# RFWBBoard.net
KiCad netlist of a schematic drawn in EAGLE
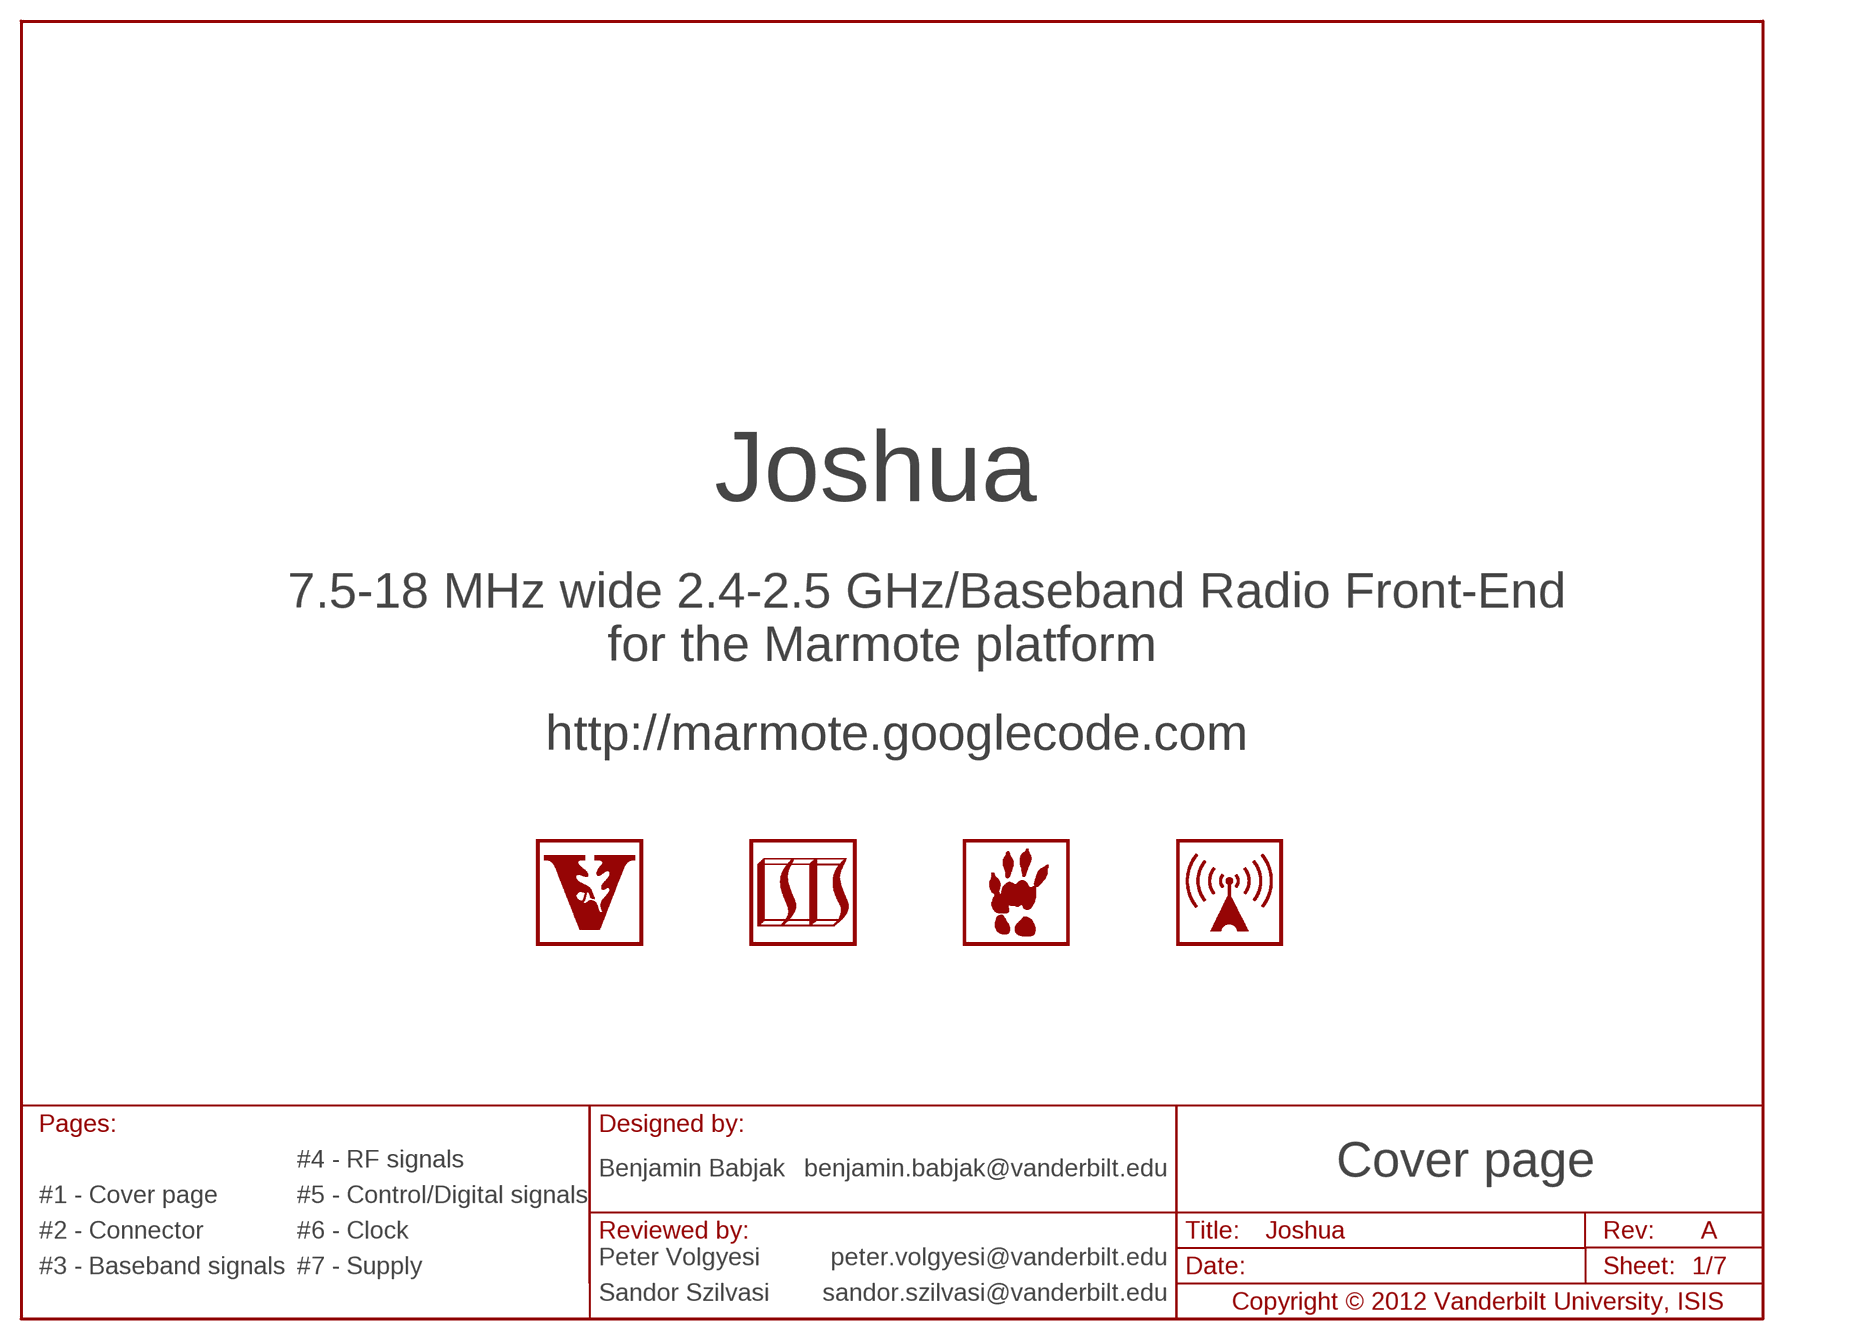
[diagram p0: schematic, sheet 1]
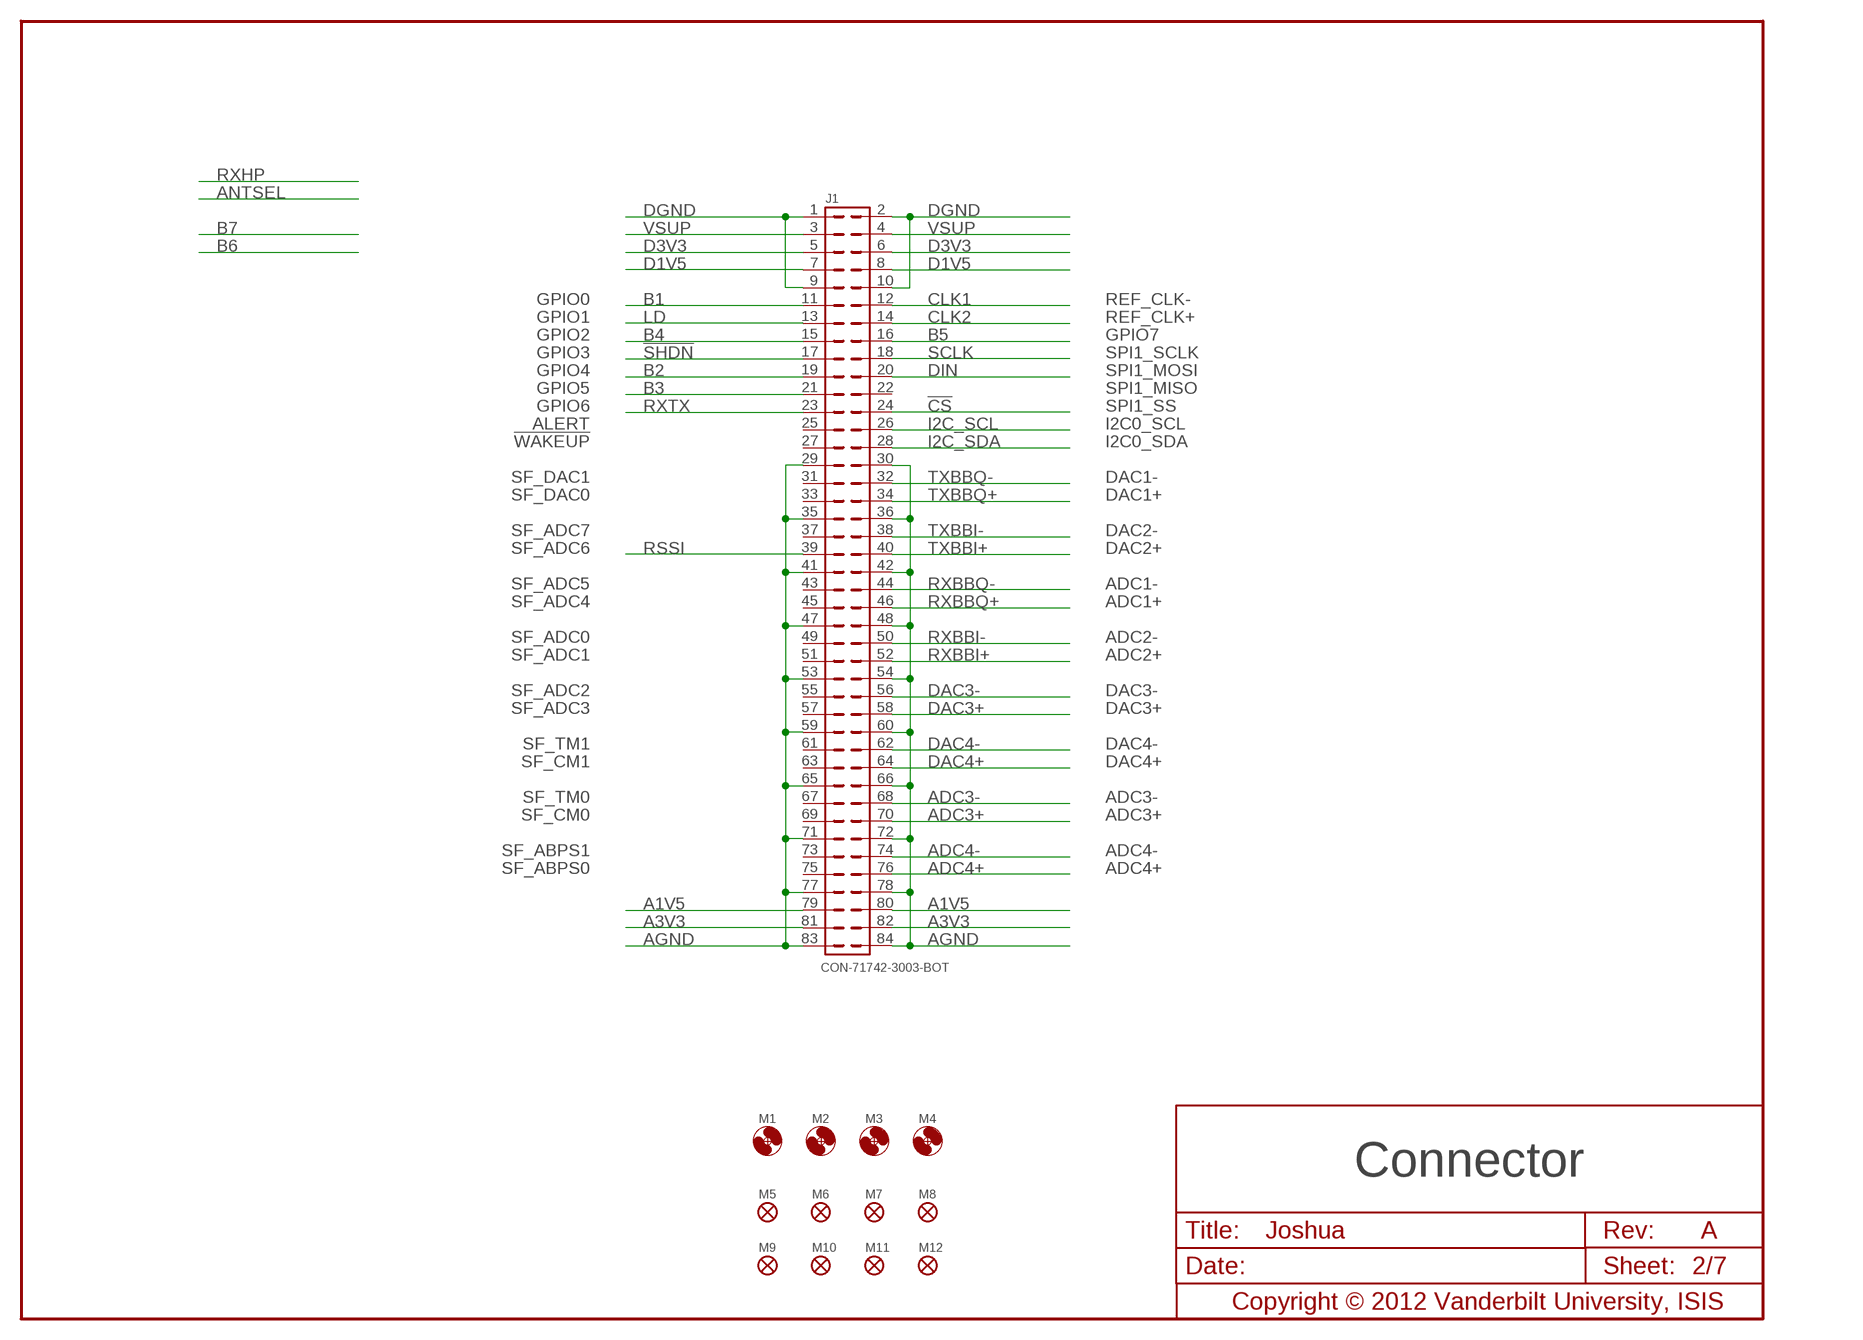
[diagram p1: schematic, sheet 2]
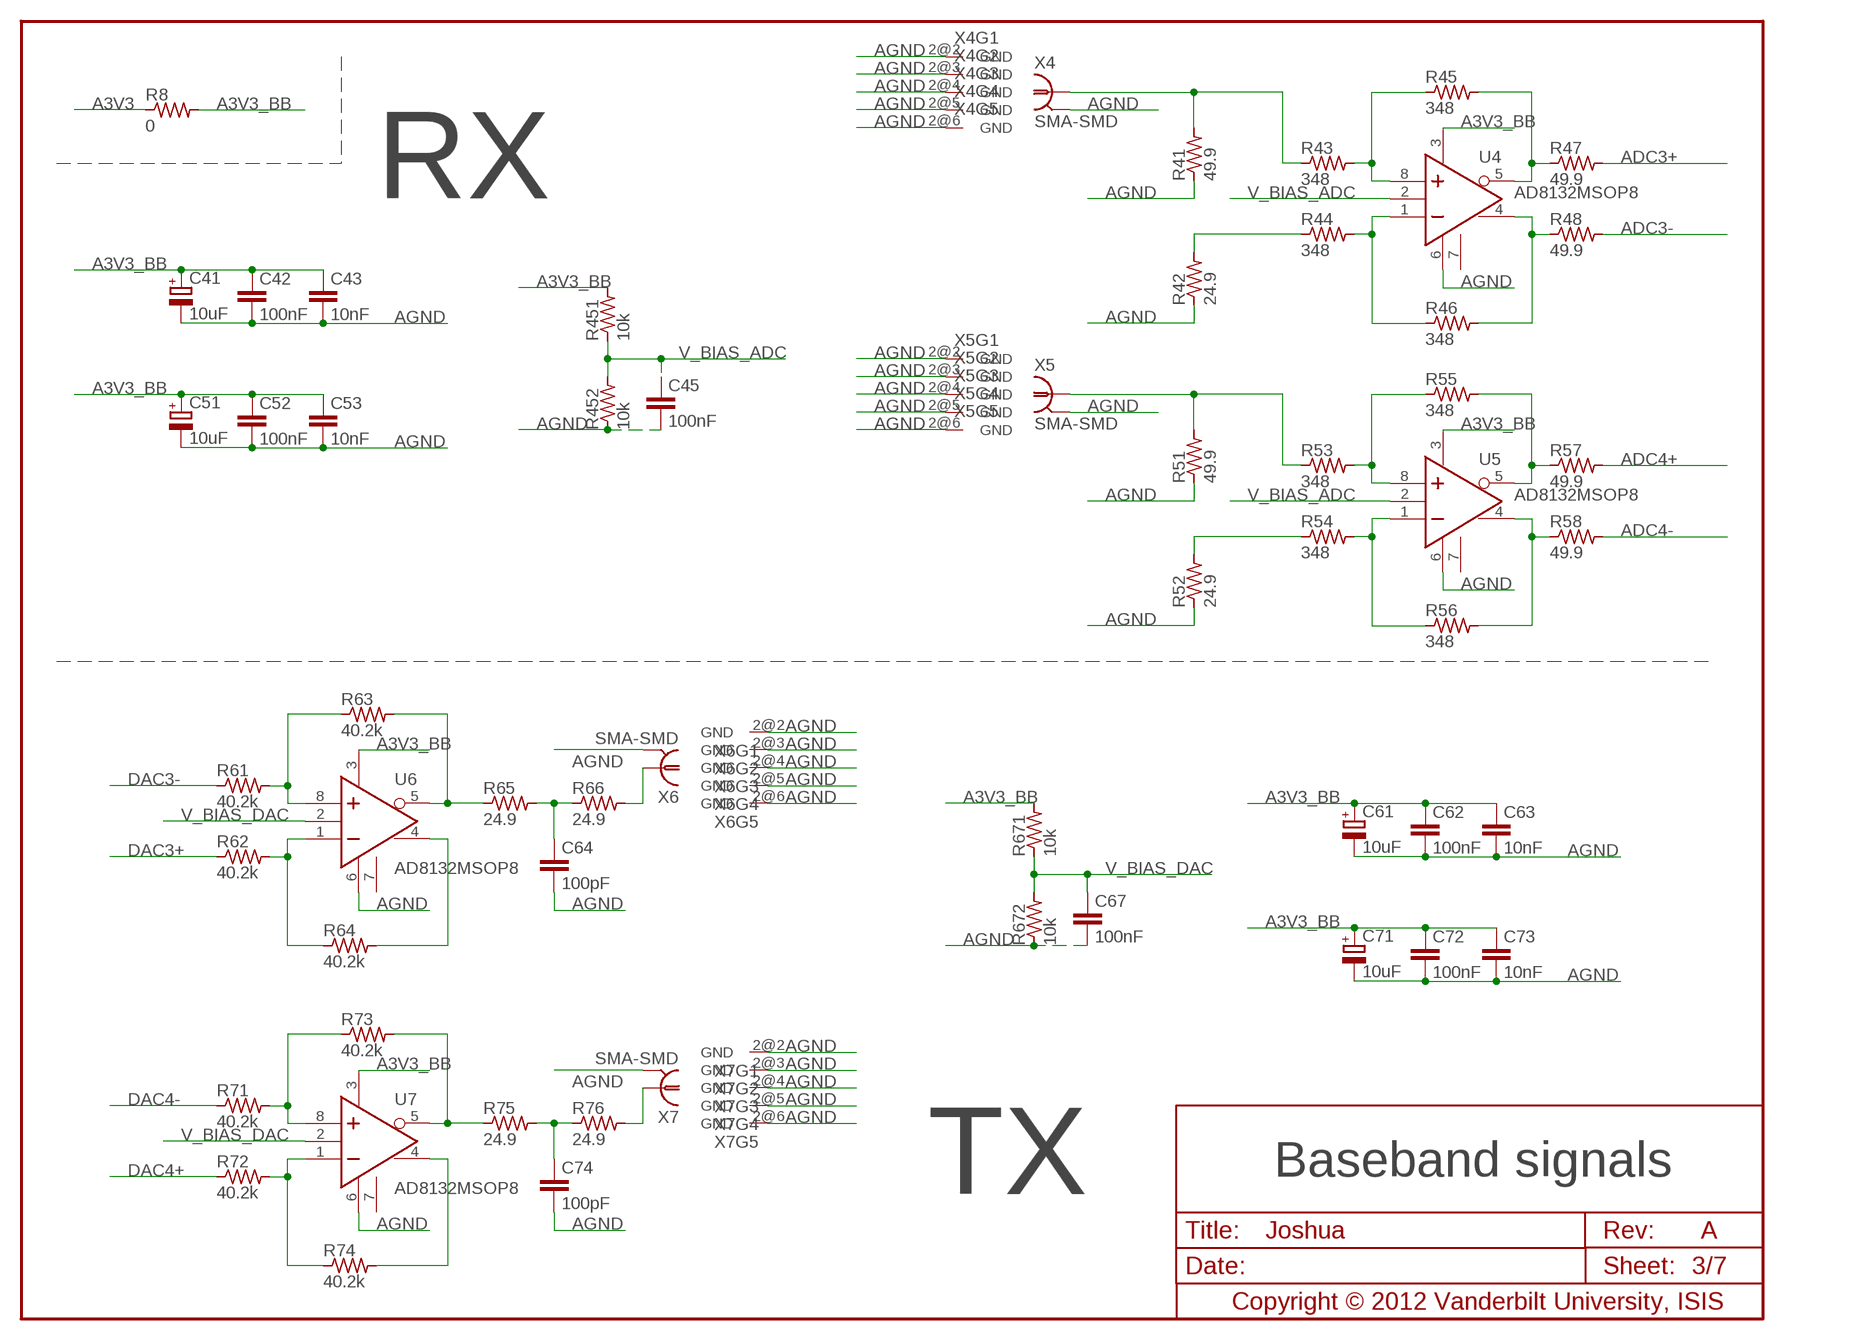
[diagram p2: schematic, sheet 3]
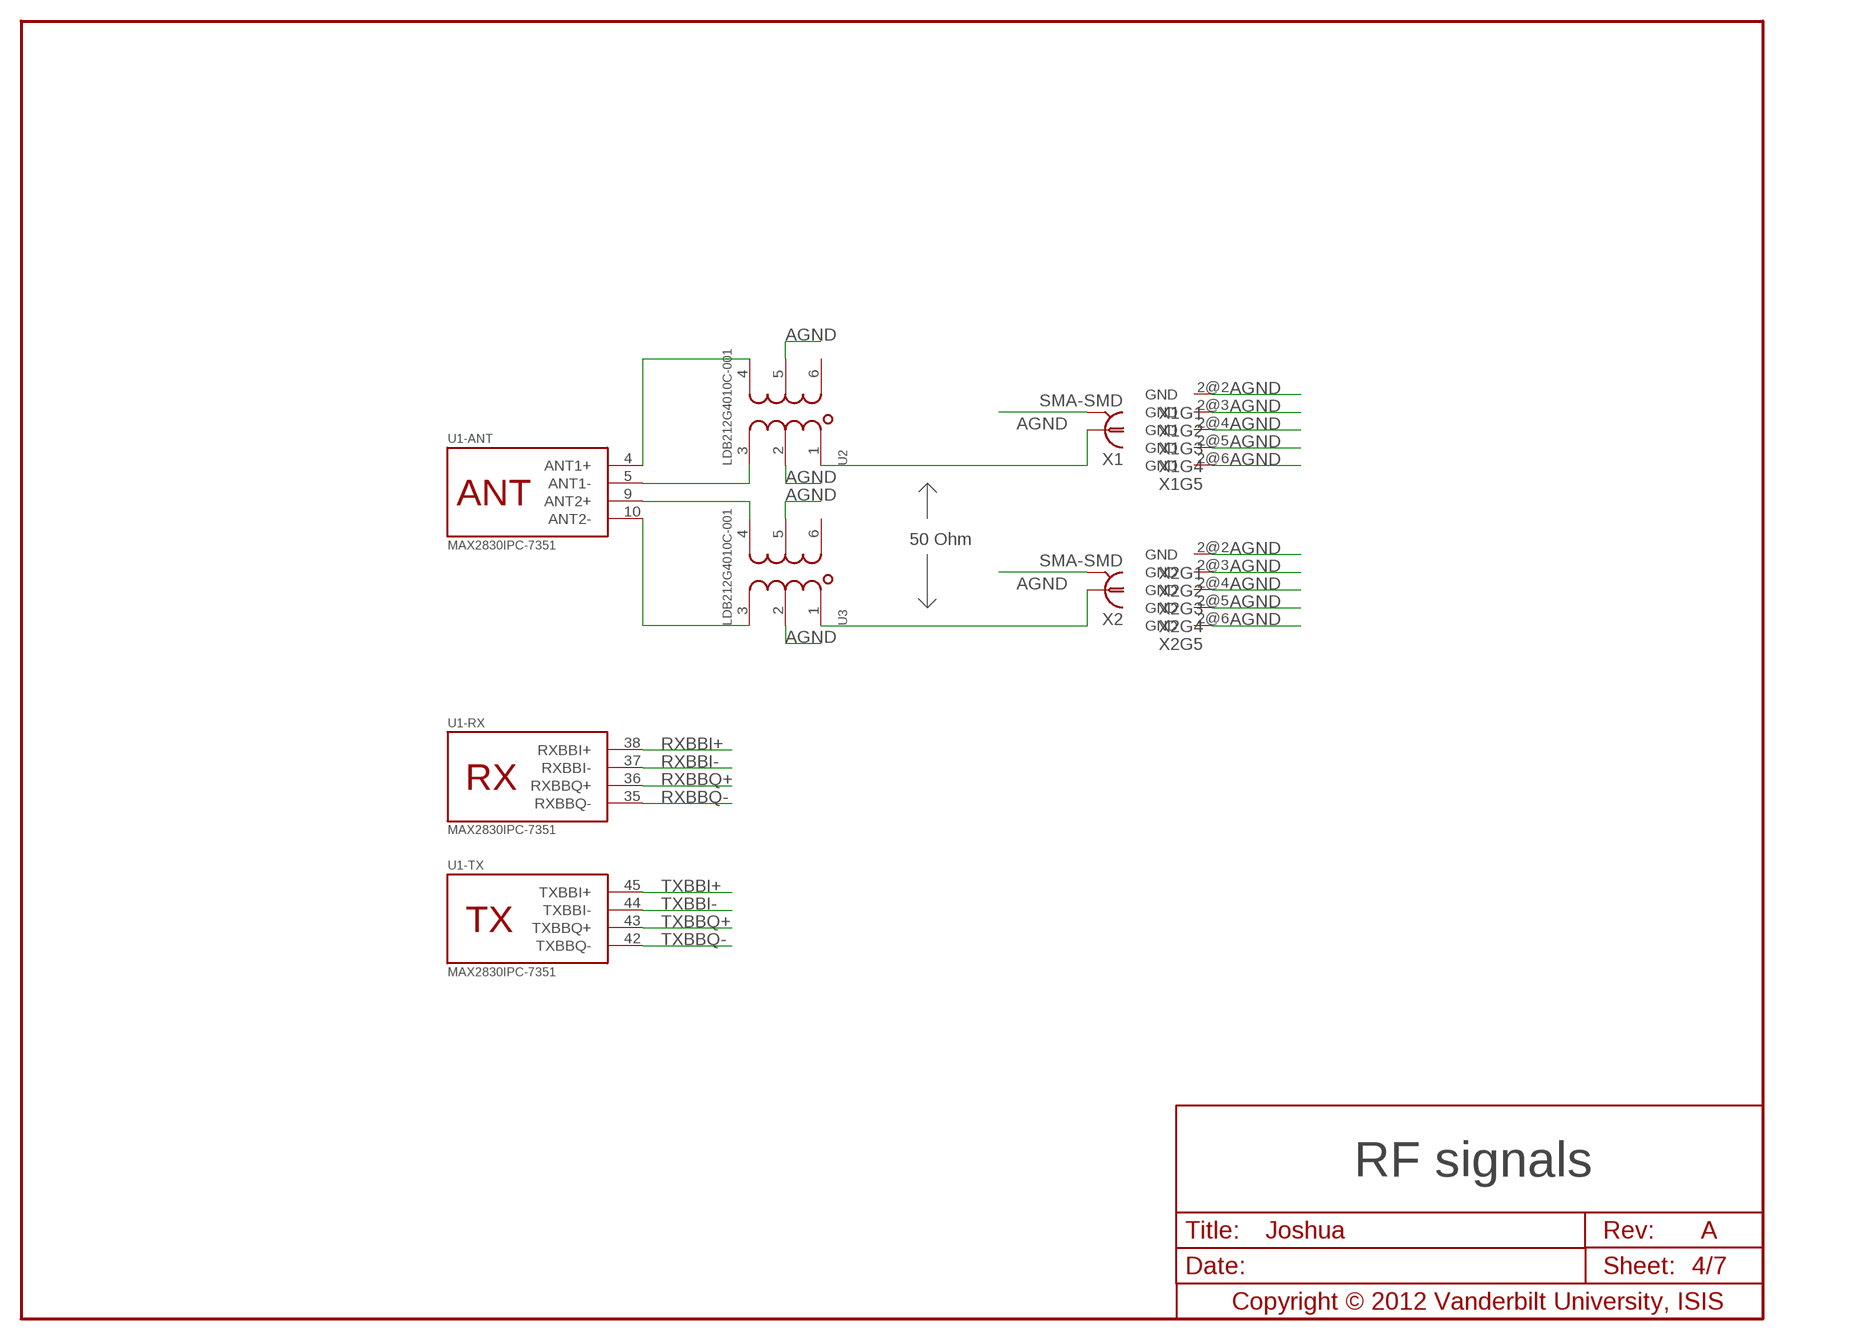
[diagram p3: schematic, sheet 4]
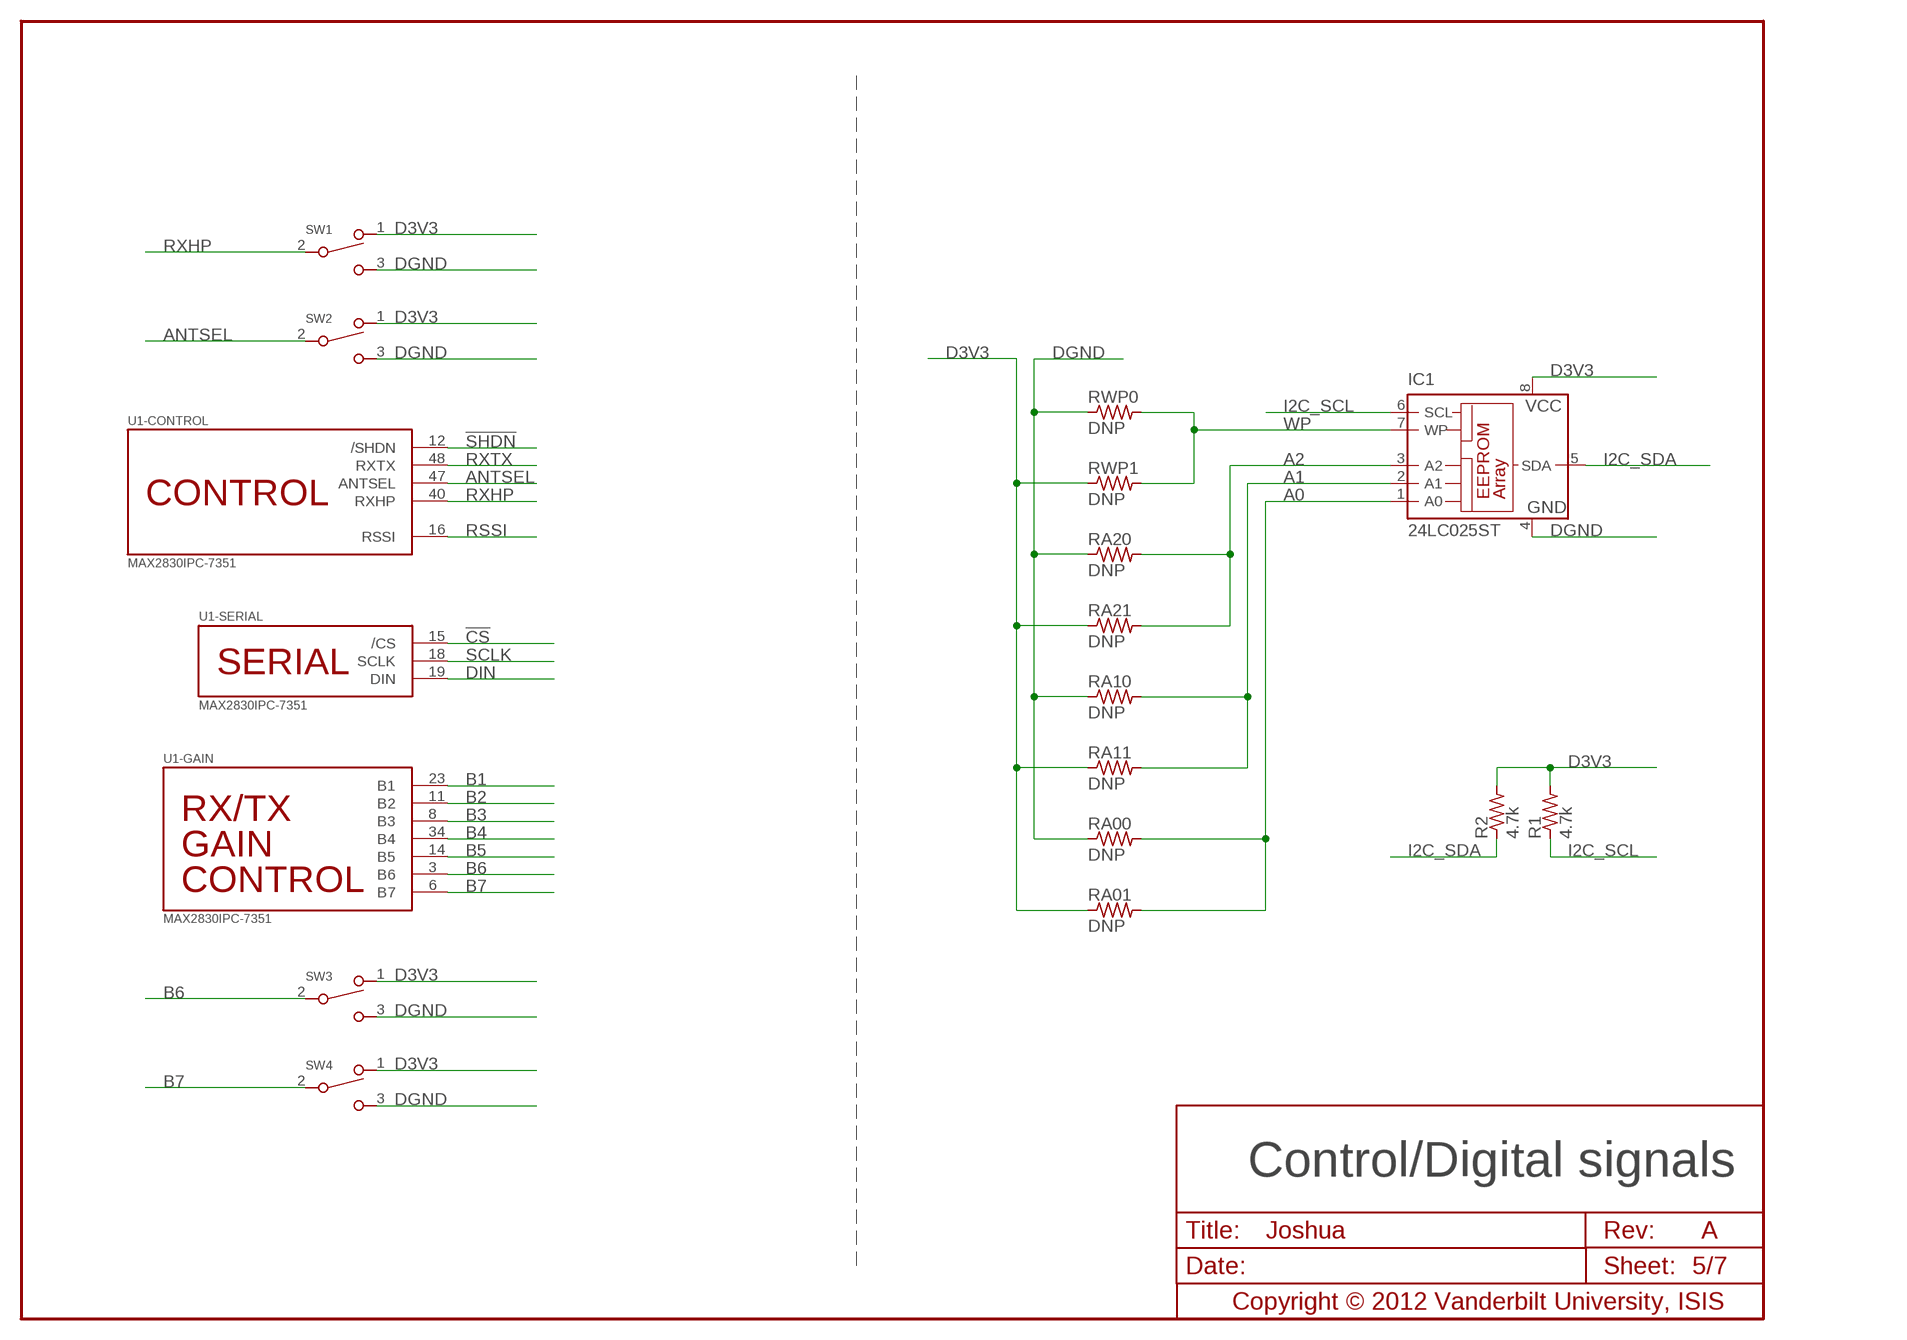
[diagram p4: schematic, sheet 5]
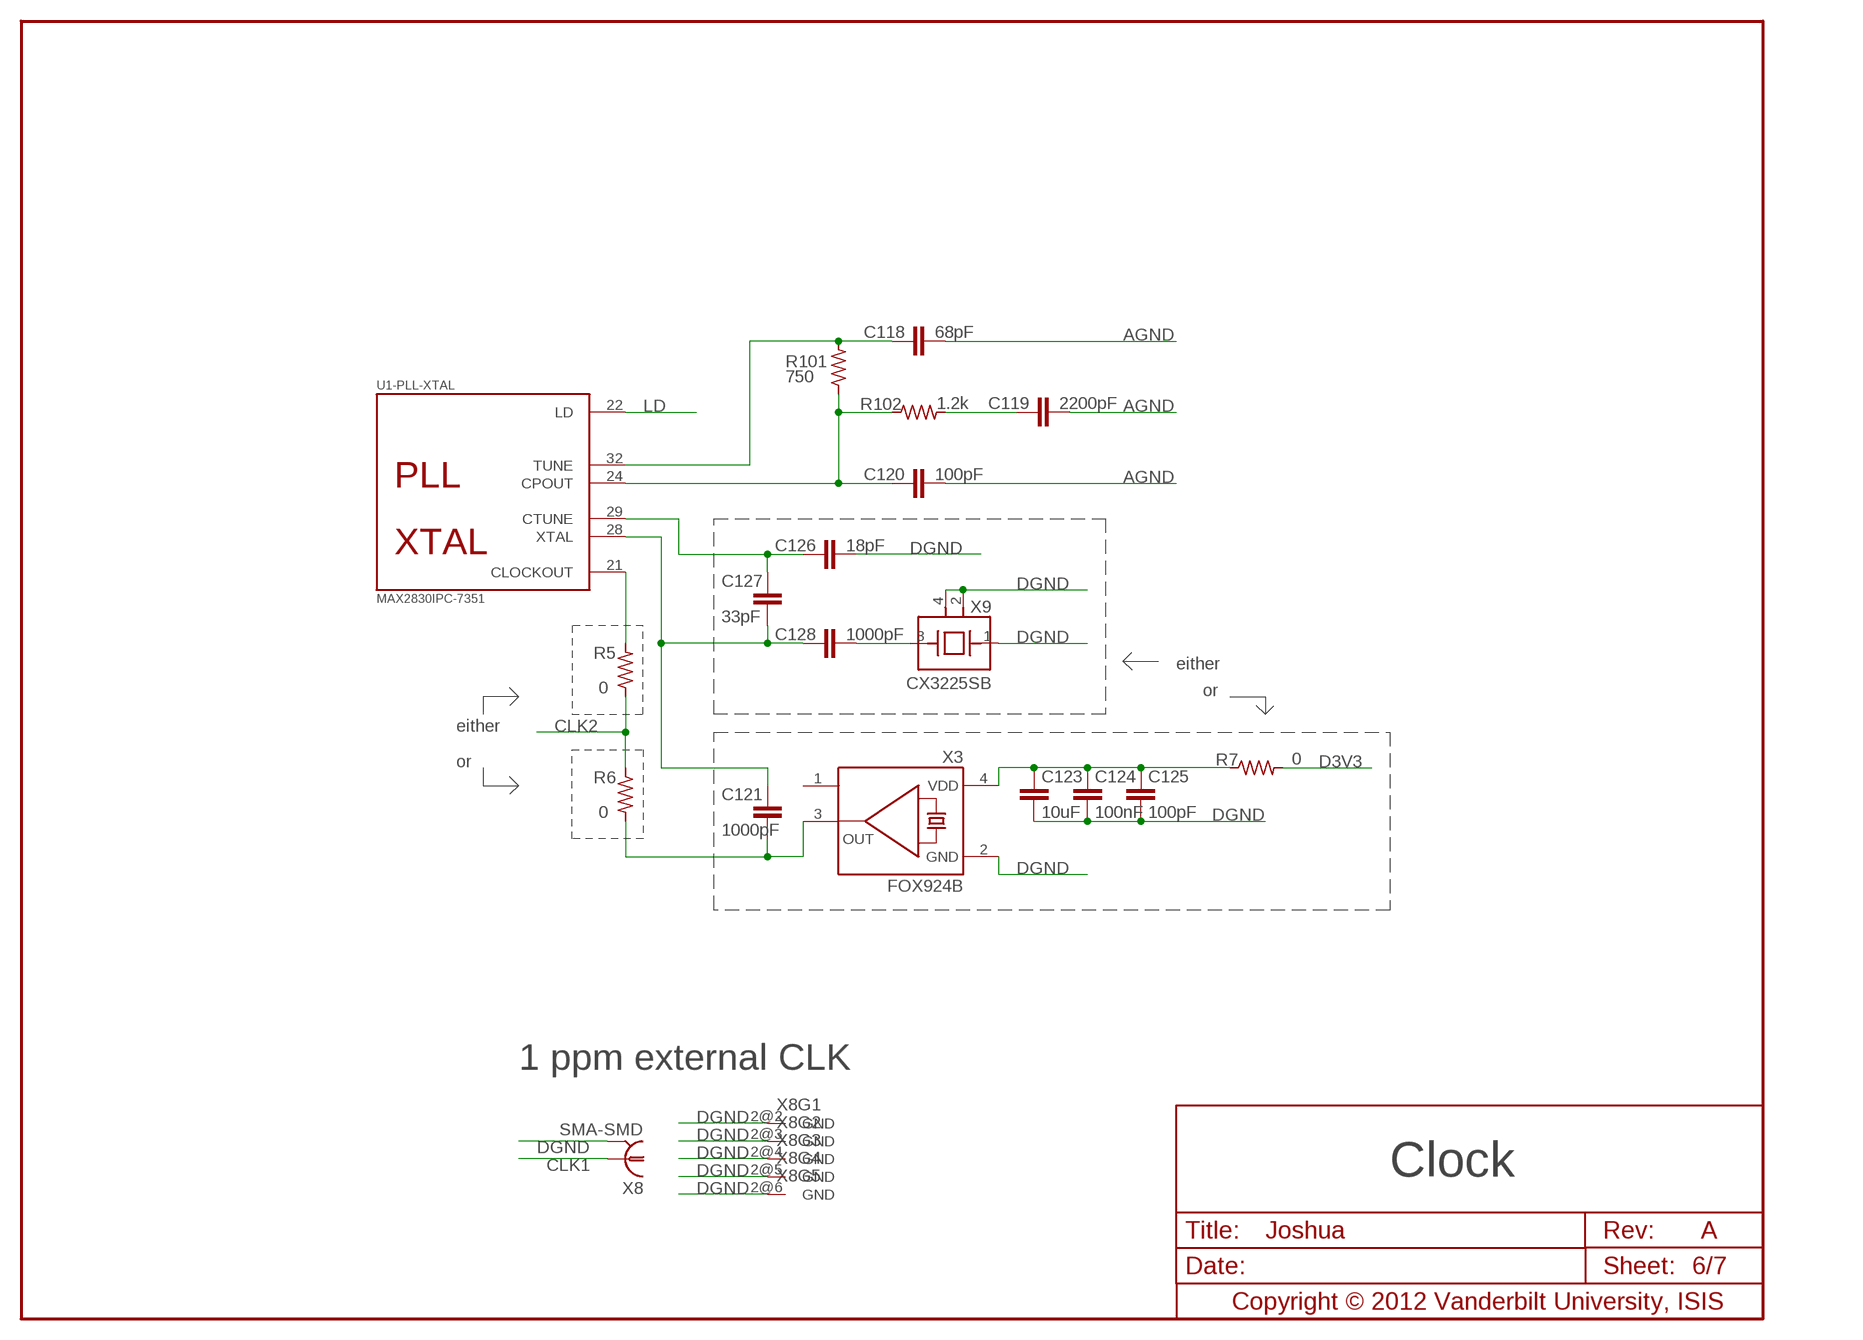
[diagram p5: schematic, sheet 6]
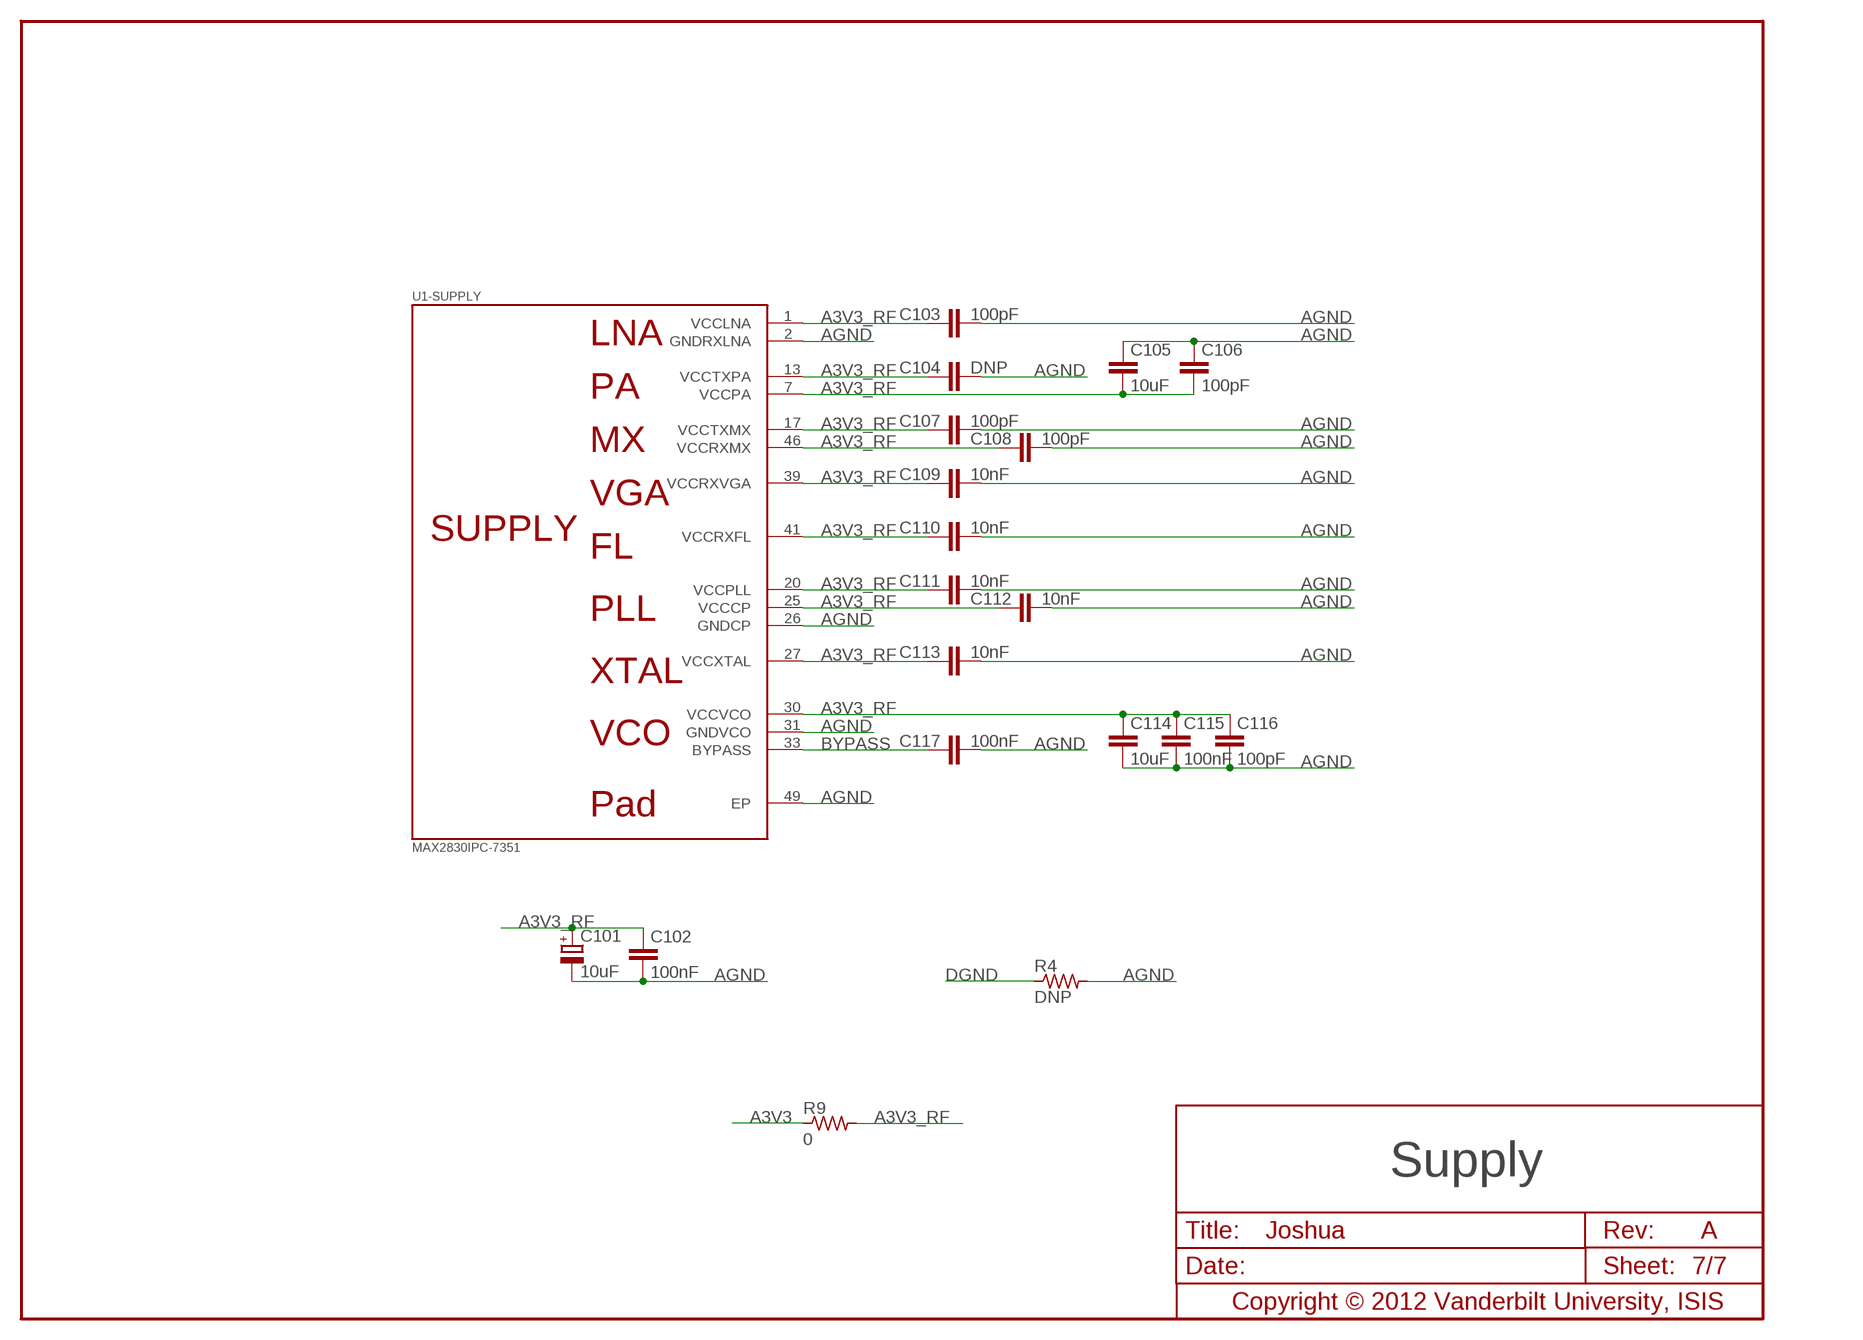
[diagram p6: schematic, sheet 7]

(export (version "E")
  (design (tool "Eeschema 10.0.6"))
  (components
    (comp (ref "C101")
      (value "10uF")
      (footprint "eagle-import:CPOL2012")
      (libsource (lib "eagle-import") (part "CPOL2012"))
    )
    (comp (ref "C102")
      (value "100nF")
      (footprint "eagle-import:C0402")
      (libsource (lib "eagle-import") (part "C0402"))
    )
    (comp (ref "C103")
      (value "100pF")
      (footprint "eagle-import:C0402")
      (libsource (lib "eagle-import") (part "C0402"))
    )
    (comp (ref "C104")
      (value "DNP")
      (footprint "eagle-import:C0402")
      (libsource (lib "eagle-import") (part "C0402"))
    )
    (comp (ref "C105")
      (value "10uF")
      (footprint "eagle-import:C1206")
      (libsource (lib "eagle-import") (part "C1206"))
    )
    (comp (ref "C106")
      (value "100pF")
      (footprint "eagle-import:C0402")
      (libsource (lib "eagle-import") (part "C0402"))
    )
    (comp (ref "C107")
      (value "100pF")
      (footprint "eagle-import:C0402")
      (libsource (lib "eagle-import") (part "C0402"))
    )
    (comp (ref "C108")
      (value "100pF")
      (footprint "eagle-import:C0402")
      (libsource (lib "eagle-import") (part "C0402"))
    )
    (comp (ref "C109")
      (value "10nF")
      (footprint "eagle-import:C0402")
      (libsource (lib "eagle-import") (part "C0402"))
    )
    (comp (ref "C110")
      (value "10nF")
      (footprint "eagle-import:C0402")
      (libsource (lib "eagle-import") (part "C0402"))
    )
    (comp (ref "C111")
      (value "10nF")
      (footprint "eagle-import:C0402")
      (libsource (lib "eagle-import") (part "C0402"))
    )
    (comp (ref "C112")
      (value "10nF")
      (footprint "eagle-import:C0402")
      (libsource (lib "eagle-import") (part "C0402"))
    )
    (comp (ref "C113")
      (value "10nF")
      (footprint "eagle-import:C0402")
      (libsource (lib "eagle-import") (part "C0402"))
    )
    (comp (ref "C114")
      (value "10uF")
      (footprint "eagle-import:C0805")
      (libsource (lib "eagle-import") (part "C0805"))
    )
    (comp (ref "C115")
      (value "100nF")
      (footprint "eagle-import:C0402")
      (libsource (lib "eagle-import") (part "C0402"))
    )
    (comp (ref "C116")
      (value "100pF")
      (footprint "eagle-import:C0402")
      (libsource (lib "eagle-import") (part "C0402"))
    )
    (comp (ref "C117")
      (value "100nF")
      (footprint "eagle-import:C0402")
      (libsource (lib "eagle-import") (part "C0402"))
    )
    (comp (ref "R4")
      (value "DNP")
      (footprint "eagle-import:R1206")
      (libsource (lib "eagle-import") (part "R1206"))
    )
    (comp (ref "R9")
      (value "0")
      (footprint "eagle-import:R1206")
      (libsource (lib "eagle-import") (part "R1206"))
    )
    (comp (ref "U1")
      (value "MAX2830IPC-7351")
      (footprint "eagle-import:TQFN-48")
      (libsource (lib "eagle-import") (part "MAX2830IPC-7351"))
    )
    (comp (ref "IC1")
      (value "24LC025ST")
      (footprint "eagle-import:TSSOP8")
      (fields (field (name "MF") "MICROCHIP") (field (name "MPN") "24LC025-I/ST"))
      (libsource (lib "eagle-import") (part "24STLC025"))
    )
    (comp (ref "R1")
      (value "4.7k")
      (footprint "eagle-import:R0402")
      (libsource (lib "eagle-import") (part "R0402"))
    )
    (comp (ref "R2")
      (value "4.7k")
      (footprint "eagle-import:R0402")
      (libsource (lib "eagle-import") (part "R0402"))
    )
    (comp (ref "RA00")
      (value "DNP")
      (footprint "eagle-import:R0402")
      (libsource (lib "eagle-import") (part "R0402"))
    )
    (comp (ref "RA01")
      (value "DNP")
      (footprint "eagle-import:R0402")
      (libsource (lib "eagle-import") (part "R0402"))
    )
    (comp (ref "RA10")
      (value "DNP")
      (footprint "eagle-import:R0402")
      (libsource (lib "eagle-import") (part "R0402"))
    )
    (comp (ref "RA11")
      (value "DNP")
      (footprint "eagle-import:R0402")
      (libsource (lib "eagle-import") (part "R0402"))
    )
    (comp (ref "RA20")
      (value "DNP")
      (footprint "eagle-import:R0402")
      (libsource (lib "eagle-import") (part "R0402"))
    )
    (comp (ref "RA21")
      (value "DNP")
      (footprint "eagle-import:R0402")
      (libsource (lib "eagle-import") (part "R0402"))
    )
    (comp (ref "RWP0")
      (value "DNP")
      (footprint "eagle-import:R0402")
      (libsource (lib "eagle-import") (part "R0402"))
    )
    (comp (ref "RWP1")
      (value "DNP")
      (footprint "eagle-import:R0402")
      (libsource (lib "eagle-import") (part "R0402"))
    )
    (comp (ref "SW1")
      (value "SWITCH-CJS-1200TA")
      (footprint "eagle-import:SWITCH-DIP-CJS")
      (fields (field (name "MF") "CJS") (field (name "MPN") "CJS-1200TA"))
      (libsource (lib "eagle-import") (part "SWITCH-CJS-1200TA"))
    )
    (comp (ref "SW2")
      (value "SWITCH-CJS-1200TA")
      (footprint "eagle-import:SWITCH-DIP-CJS")
      (fields (field (name "MF") "CJS") (field (name "MPN") "CJS-1200TA"))
      (libsource (lib "eagle-import") (part "SWITCH-CJS-1200TA"))
    )
    (comp (ref "SW3")
      (value "SWITCH-CJS-1200TA")
      (footprint "eagle-import:SWITCH-DIP-CJS")
      (fields (field (name "MF") "CJS") (field (name "MPN") "CJS-1200TA"))
      (libsource (lib "eagle-import") (part "SWITCH-CJS-1200TA"))
    )
    (comp (ref "SW4")
      (value "SWITCH-CJS-1200TA")
      (footprint "eagle-import:SWITCH-DIP-CJS")
      (fields (field (name "MF") "CJS") (field (name "MPN") "CJS-1200TA"))
      (libsource (lib "eagle-import") (part "SWITCH-CJS-1200TA"))
    )
    (comp (ref "J1")
      (value "CON-71742-3003-BOT")
      (footprint "eagle-import:71742-3003-BOT")
      (libsource (lib "eagle-import") (part "CON-71742-3003-BOT"))
    )
    (comp (ref "M1")
      (value "MOUNT-HOLE3.3")
      (footprint "eagle-import:3,3")
      (libsource (lib "eagle-import") (part "MOUNT-HOLE3.3"))
    )
    (comp (ref "M2")
      (value "MOUNT-HOLE3.3")
      (footprint "eagle-import:3,3")
      (libsource (lib "eagle-import") (part "MOUNT-HOLE3.3"))
    )
    (comp (ref "M3")
      (value "MOUNT-HOLE3.3")
      (footprint "eagle-import:3,3")
      (libsource (lib "eagle-import") (part "MOUNT-HOLE3.3"))
    )
    (comp (ref "M4")
      (value "MOUNT-HOLE3.3")
      (footprint "eagle-import:3,3")
      (libsource (lib "eagle-import") (part "MOUNT-HOLE3.3"))
    )
    (comp (ref "M5")
      (value "FIDUCIAL1X2")
      (footprint "eagle-import:FIDUCIAL-1X2")
      (libsource (lib "eagle-import") (part "FIDUCIAL1X2"))
    )
    (comp (ref "M6")
      (value "FIDUCIAL1X2")
      (footprint "eagle-import:FIDUCIAL-1X2")
      (libsource (lib "eagle-import") (part "FIDUCIAL1X2"))
    )
    (comp (ref "M7")
      (value "FIDUCIAL1X2")
      (footprint "eagle-import:FIDUCIAL-1X2")
      (libsource (lib "eagle-import") (part "FIDUCIAL1X2"))
    )
    (comp (ref "M8")
      (value "FIDUCIAL1X2")
      (footprint "eagle-import:FIDUCIAL-1X2")
      (libsource (lib "eagle-import") (part "FIDUCIAL1X2"))
    )
    (comp (ref "M9")
      (value "FIDUCIAL1X2")
      (footprint "eagle-import:FIDUCIAL-1X2")
      (libsource (lib "eagle-import") (part "FIDUCIAL1X2"))
    )
    (comp (ref "M10")
      (value "FIDUCIAL1X2")
      (footprint "eagle-import:FIDUCIAL-1X2")
      (libsource (lib "eagle-import") (part "FIDUCIAL1X2"))
    )
    (comp (ref "M11")
      (value "FIDUCIAL1X2")
      (footprint "eagle-import:FIDUCIAL-1X2")
      (libsource (lib "eagle-import") (part "FIDUCIAL1X2"))
    )
    (comp (ref "M12")
      (value "FIDUCIAL1X2")
      (footprint "eagle-import:FIDUCIAL-1X2")
      (libsource (lib "eagle-import") (part "FIDUCIAL1X2"))
    )
    (comp (ref "U2")
      (value "LDB212G4010C-001")
      (footprint "eagle-import:LDB21-FOOTPRINT")
      (libsource (lib "eagle-import") (part "LDB212G4010C-001"))
    )
    (comp (ref "U3")
      (value "LDB212G4010C-001")
      (footprint "eagle-import:LDB21-FOOTPRINT")
      (libsource (lib "eagle-import") (part "LDB212G4010C-001"))
    )
    (comp (ref "X1")
      (value "SMA-SMD")
      (footprint "eagle-import:SMA-SMD")
      (libsource (lib "eagle-import") (part "SMA-SMD"))
    )
    (comp (ref "X2")
      (value "SMA-SMD")
      (footprint "eagle-import:SMA-SMD")
      (libsource (lib "eagle-import") (part "SMA-SMD"))
    )
    (comp (ref "LOGO4")
      (value "LOGO-ISIS-600MIL-10MM-SS")
      (footprint "eagle-import:LOGO-ISIS-10MM-SILKSCREEN")
      (libsource (lib "eagle-import") (part "LOGO-ISIS-600MIL-10MM-SS"))
    )
    (comp (ref "LOGO5")
      (value "LOGO-VANDERBILT-600MIL-10MM-SS")
      (footprint "eagle-import:LOGO-VANDERBILT-10MM-SILKSCREEN")
      (libsource (lib "eagle-import") (part "LOGO-VANDERBILT-600MIL-10MM-SS"))
    )
    (comp (ref "LOGO6")
      (value "LOGO-MARMOTE-600MIL-10MM-SS")
      (footprint "eagle-import:LOGO-MARMOTE-10MM-SILKSCREEN")
      (libsource (lib "eagle-import") (part "LOGO-MARMOTE-600MIL-10MM-SS"))
    )
    (comp (ref "LOGO7")
      (value "LOGO-RADIO-3-600MIL-10MM-SS")
      (footprint "eagle-import:LOGO-RADIO-FILLED-10MM-SILKSCREEN")
      (libsource (lib "eagle-import") (part "LOGO-RADIO-3-600MIL-10MM-SS"))
    )
    (comp (ref "C41")
      (value "10uF")
      (footprint "eagle-import:CPOL2012")
      (libsource (lib "eagle-import") (part "CPOL2012"))
    )
    (comp (ref "C42")
      (value "100nF")
      (footprint "eagle-import:C0402")
      (libsource (lib "eagle-import") (part "C0402"))
    )
    (comp (ref "C43")
      (value "10nF")
      (footprint "eagle-import:C0402")
      (libsource (lib "eagle-import") (part "C0402"))
    )
    (comp (ref "C45")
      (value "100nF")
      (footprint "eagle-import:C0402")
      (libsource (lib "eagle-import") (part "C0402"))
    )
    (comp (ref "C51")
      (value "10uF")
      (footprint "eagle-import:CPOL2012")
      (libsource (lib "eagle-import") (part "CPOL2012"))
    )
    (comp (ref "C52")
      (value "100nF")
      (footprint "eagle-import:C0402")
      (libsource (lib "eagle-import") (part "C0402"))
    )
    (comp (ref "C53")
      (value "10nF")
      (footprint "eagle-import:C0402")
      (libsource (lib "eagle-import") (part "C0402"))
    )
    (comp (ref "C61")
      (value "10uF")
      (footprint "eagle-import:CPOL2012")
      (libsource (lib "eagle-import") (part "CPOL2012"))
    )
    (comp (ref "C62")
      (value "100nF")
      (footprint "eagle-import:C0402")
      (libsource (lib "eagle-import") (part "C0402"))
    )
    (comp (ref "C63")
      (value "10nF")
      (footprint "eagle-import:C0402")
      (libsource (lib "eagle-import") (part "C0402"))
    )
    (comp (ref "C64")
      (value "100pF")
      (footprint "eagle-import:C0402")
      (libsource (lib "eagle-import") (part "C0402"))
    )
    (comp (ref "C67")
      (value "100nF")
      (footprint "eagle-import:C0402")
      (libsource (lib "eagle-import") (part "C0402"))
    )
    (comp (ref "C71")
      (value "10uF")
      (footprint "eagle-import:CPOL2012")
      (libsource (lib "eagle-import") (part "CPOL2012"))
    )
    (comp (ref "C72")
      (value "100nF")
      (footprint "eagle-import:C0402")
      (libsource (lib "eagle-import") (part "C0402"))
    )
    (comp (ref "C73")
      (value "10nF")
      (footprint "eagle-import:C0402")
      (libsource (lib "eagle-import") (part "C0402"))
    )
    (comp (ref "C74")
      (value "100pF")
      (footprint "eagle-import:C0402")
      (libsource (lib "eagle-import") (part "C0402"))
    )
    (comp (ref "R8")
      (value "0")
      (footprint "eagle-import:R1206")
      (libsource (lib "eagle-import") (part "R1206"))
    )
    (comp (ref "R41")
      (value "49.9")
      (footprint "eagle-import:R0402")
      (libsource (lib "eagle-import") (part "R0402"))
    )
    (comp (ref "R42")
      (value "24.9")
      (footprint "eagle-import:R0402")
      (libsource (lib "eagle-import") (part "R0402"))
    )
    (comp (ref "R43")
      (value "348")
      (footprint "eagle-import:R0402")
      (libsource (lib "eagle-import") (part "R0402"))
    )
    (comp (ref "R44")
      (value "348")
      (footprint "eagle-import:R0402")
      (libsource (lib "eagle-import") (part "R0402"))
    )
    (comp (ref "R45")
      (value "348")
      (footprint "eagle-import:R0402")
      (libsource (lib "eagle-import") (part "R0402"))
    )
    (comp (ref "R46")
      (value "348")
      (footprint "eagle-import:R0402")
      (libsource (lib "eagle-import") (part "R0402"))
    )
    (comp (ref "R47")
      (value "49.9")
      (footprint "eagle-import:R0402")
      (libsource (lib "eagle-import") (part "R0402"))
    )
    (comp (ref "R48")
      (value "49.9")
      (footprint "eagle-import:R0402")
      (libsource (lib "eagle-import") (part "R0402"))
    )
    (comp (ref "R51")
      (value "49.9")
      (footprint "eagle-import:R0402")
      (libsource (lib "eagle-import") (part "R0402"))
    )
    (comp (ref "R52")
      (value "24.9")
      (footprint "eagle-import:R0402")
      (libsource (lib "eagle-import") (part "R0402"))
    )
    (comp (ref "R53")
      (value "348")
      (footprint "eagle-import:R0402")
      (libsource (lib "eagle-import") (part "R0402"))
    )
    (comp (ref "R54")
      (value "348")
      (footprint "eagle-import:R0402")
      (libsource (lib "eagle-import") (part "R0402"))
    )
    (comp (ref "R55")
      (value "348")
      (footprint "eagle-import:R0402")
      (libsource (lib "eagle-import") (part "R0402"))
    )
    (comp (ref "R56")
      (value "348")
      (footprint "eagle-import:R0402")
      (libsource (lib "eagle-import") (part "R0402"))
    )
    (comp (ref "R57")
      (value "49.9")
      (footprint "eagle-import:R0402")
      (libsource (lib "eagle-import") (part "R0402"))
    )
    (comp (ref "R58")
      (value "49.9")
      (footprint "eagle-import:R0402")
      (libsource (lib "eagle-import") (part "R0402"))
    )
    (comp (ref "R61")
      (value "40.2k")
      (footprint "eagle-import:R0402")
      (libsource (lib "eagle-import") (part "R0402"))
    )
    (comp (ref "R62")
      (value "40.2k")
      (footprint "eagle-import:R0402")
      (libsource (lib "eagle-import") (part "R0402"))
    )
    (comp (ref "R63")
      (value "40.2k")
      (footprint "eagle-import:R0402")
      (libsource (lib "eagle-import") (part "R0402"))
    )
    (comp (ref "R64")
      (value "40.2k")
      (footprint "eagle-import:R0402")
      (libsource (lib "eagle-import") (part "R0402"))
    )
    (comp (ref "R65")
      (value "24.9")
      (footprint "eagle-import:R0402")
      (libsource (lib "eagle-import") (part "R0402"))
    )
    (comp (ref "R66")
      (value "24.9")
      (footprint "eagle-import:R0402")
      (libsource (lib "eagle-import") (part "R0402"))
    )
    (comp (ref "R71")
      (value "40.2k")
      (footprint "eagle-import:R0402")
      (libsource (lib "eagle-import") (part "R0402"))
    )
    (comp (ref "R72")
      (value "40.2k")
      (footprint "eagle-import:R0402")
      (libsource (lib "eagle-import") (part "R0402"))
    )
    (comp (ref "R73")
      (value "40.2k")
      (footprint "eagle-import:R0402")
      (libsource (lib "eagle-import") (part "R0402"))
    )
    (comp (ref "R74")
      (value "40.2k")
      (footprint "eagle-import:R0402")
      (libsource (lib "eagle-import") (part "R0402"))
    )
    (comp (ref "R75")
      (value "24.9")
      (footprint "eagle-import:R0402")
      (libsource (lib "eagle-import") (part "R0402"))
    )
    (comp (ref "R76")
      (value "24.9")
      (footprint "eagle-import:R0402")
      (libsource (lib "eagle-import") (part "R0402"))
    )
    (comp (ref "R451")
      (value "10k")
      (footprint "eagle-import:R0402")
      (libsource (lib "eagle-import") (part "R0402"))
    )
    (comp (ref "R452")
      (value "10k")
      (footprint "eagle-import:R0402")
      (libsource (lib "eagle-import") (part "R0402"))
    )
    (comp (ref "R671")
      (value "10k")
      (footprint "eagle-import:R0402")
      (libsource (lib "eagle-import") (part "R0402"))
    )
    (comp (ref "R672")
      (value "10k")
      (footprint "eagle-import:R0402")
      (libsource (lib "eagle-import") (part "R0402"))
    )
    (comp (ref "U4")
      (value "AD8132MSOP8")
      (footprint "eagle-import:MSOP8")
      (libsource (lib "eagle-import") (part "AD8132MSOP8"))
    )
    (comp (ref "U5")
      (value "AD8132MSOP8")
      (footprint "eagle-import:MSOP8")
      (libsource (lib "eagle-import") (part "AD8132MSOP8"))
    )
    (comp (ref "U6")
      (value "AD8132MSOP8")
      (footprint "eagle-import:MSOP8")
      (libsource (lib "eagle-import") (part "AD8132MSOP8"))
    )
    (comp (ref "U7")
      (value "AD8132MSOP8")
      (footprint "eagle-import:MSOP8")
      (libsource (lib "eagle-import") (part "AD8132MSOP8"))
    )
    (comp (ref "X4")
      (value "SMA-SMD")
      (footprint "eagle-import:SMA-SMD")
      (libsource (lib "eagle-import") (part "SMA-SMD"))
    )
    (comp (ref "X5")
      (value "SMA-SMD")
      (footprint "eagle-import:SMA-SMD")
      (libsource (lib "eagle-import") (part "SMA-SMD"))
    )
    (comp (ref "X6")
      (value "SMA-SMD")
      (footprint "eagle-import:SMA-SMD")
      (libsource (lib "eagle-import") (part "SMA-SMD"))
    )
    (comp (ref "X7")
      (value "SMA-SMD")
      (footprint "eagle-import:SMA-SMD")
      (libsource (lib "eagle-import") (part "SMA-SMD"))
    )
    (comp (ref "C118")
      (value "68pF")
      (footprint "eagle-import:C0402")
      (libsource (lib "eagle-import") (part "C0402"))
    )
    (comp (ref "C119")
      (value "2200pF")
      (footprint "eagle-import:C0402")
      (libsource (lib "eagle-import") (part "C0402"))
    )
    (comp (ref "C120")
      (value "100pF")
      (footprint "eagle-import:C0402")
      (libsource (lib "eagle-import") (part "C0402"))
    )
    (comp (ref "C121")
      (value "1000pF")
      (footprint "eagle-import:C0402")
      (libsource (lib "eagle-import") (part "C0402"))
    )
    (comp (ref "C123")
      (value "10uF")
      (footprint "eagle-import:C0805")
      (libsource (lib "eagle-import") (part "C0805"))
    )
    (comp (ref "C124")
      (value "100nF")
      (footprint "eagle-import:C0402")
      (libsource (lib "eagle-import") (part "C0402"))
    )
    (comp (ref "C125")
      (value "100pF")
      (footprint "eagle-import:C0402")
      (libsource (lib "eagle-import") (part "C0402"))
    )
    (comp (ref "C126")
      (value "18pF")
      (footprint "eagle-import:C0402")
      (libsource (lib "eagle-import") (part "C0402"))
    )
    (comp (ref "C127")
      (value "33pF")
      (footprint "eagle-import:C0402")
      (libsource (lib "eagle-import") (part "C0402"))
    )
    (comp (ref "C128")
      (value "1000pF")
      (footprint "eagle-import:C0402")
      (libsource (lib "eagle-import") (part "C0402"))
    )
    (comp (ref "R5")
      (value "0")
      (footprint "eagle-import:R0402")
      (libsource (lib "eagle-import") (part "R0402"))
    )
    (comp (ref "R6")
      (value "0")
      (footprint "eagle-import:R0402")
      (libsource (lib "eagle-import") (part "R0402"))
    )
    (comp (ref "R7")
      (value "0")
      (footprint "eagle-import:R1206")
      (libsource (lib "eagle-import") (part "R1206"))
    )
    (comp (ref "R101")
      (value "750")
      (footprint "eagle-import:R0402")
      (libsource (lib "eagle-import") (part "R0402"))
    )
    (comp (ref "R102")
      (value "1.2k")
      (footprint "eagle-import:R0402")
      (libsource (lib "eagle-import") (part "R0402"))
    )
    (comp (ref "X3")
      (value "FOX924B")
      (footprint "eagle-import:FOX924")
      (fields (field (name "MF") "Fox Electronics") (field (name "MPN") "FOX924B-20.000"))
      (libsource (lib "eagle-import") (part "FOX924B"))
    )
    (comp (ref "X8")
      (value "SMA-SMD")
      (footprint "eagle-import:SMA-SMD")
      (libsource (lib "eagle-import") (part "SMA-SMD"))
    )
    (comp (ref "X9")
      (value "CX3225SB")
      (footprint "eagle-import:CX3225SB")
      (libsource (lib "eagle-import") (part "CX3225SB"))
    )
  )
  (nets
    (net (code "1") (name "A0") (class "Default")
      (node (ref "IC1") (pin "1") (pinfunction "A0_1") (pintype "input"))
      (node (ref "RA00") (pin "2") (pinfunction "2_2") (pintype "passive"))
      (node (ref "RA01") (pin "2") (pinfunction "2_2") (pintype "passive"))
    )
    (net (code "2") (name "A1") (class "Default")
      (node (ref "IC1") (pin "2") (pinfunction "A1_2") (pintype "input"))
      (node (ref "RA10") (pin "2") (pinfunction "2_2") (pintype "passive"))
      (node (ref "RA11") (pin "2") (pinfunction "2_2") (pintype "passive"))
    )
    (net (code "3") (name "A1V5") (class "Default")
      (node (ref "J1") (pin "79") (pinfunction "79_79") (pintype "passive"))
      (node (ref "J1") (pin "80") (pinfunction "80_80") (pintype "passive"))
    )
    (net (code "4") (name "A2") (class "Default")
      (node (ref "IC1") (pin "3") (pinfunction "A2_3") (pintype "input"))
      (node (ref "RA20") (pin "2") (pinfunction "2_2") (pintype "passive"))
      (node (ref "RA21") (pin "2") (pinfunction "2_2") (pintype "passive"))
    )
    (net (code "5") (name "A3V3") (class "Default")
      (node (ref "J1") (pin "81") (pinfunction "81_81") (pintype "passive"))
      (node (ref "J1") (pin "82") (pinfunction "82_82") (pintype "passive"))
      (node (ref "R8") (pin "1") (pinfunction "1_1") (pintype "passive"))
      (node (ref "R9") (pin "1") (pinfunction "1_1") (pintype "passive"))
    )
    (net (code "6") (name "A3V3_BB") (class "Default")
      (node (ref "C41") (pin "+") (pinfunction "+_+") (pintype "passive"))
      (node (ref "C42") (pin "1") (pinfunction "1_1") (pintype "passive"))
      (node (ref "C43") (pin "1") (pinfunction "1_1") (pintype "passive"))
      (node (ref "C51") (pin "+") (pinfunction "+_+") (pintype "passive"))
      (node (ref "C52") (pin "1") (pinfunction "1_1") (pintype "passive"))
      (node (ref "C53") (pin "1") (pinfunction "1_1") (pintype "passive"))
      (node (ref "C61") (pin "+") (pinfunction "+_+") (pintype "passive"))
      (node (ref "C62") (pin "1") (pinfunction "1_1") (pintype "passive"))
      (node (ref "C63") (pin "1") (pinfunction "1_1") (pintype "passive"))
      (node (ref "C71") (pin "+") (pinfunction "+_+") (pintype "passive"))
      (node (ref "C72") (pin "1") (pinfunction "1_1") (pintype "passive"))
      (node (ref "C73") (pin "1") (pinfunction "1_1") (pintype "passive"))
      (node (ref "R451") (pin "2") (pinfunction "2_2") (pintype "passive"))
      (node (ref "R671") (pin "2") (pinfunction "2_2") (pintype "passive"))
      (node (ref "R8") (pin "2") (pinfunction "2_2") (pintype "passive"))
      (node (ref "U4") (pin "3") (pinfunction "V_S+_3") (pintype "power_in"))
      (node (ref "U5") (pin "3") (pinfunction "V_S+_3") (pintype "power_in"))
      (node (ref "U6") (pin "3") (pinfunction "V_S+_3") (pintype "power_in"))
      (node (ref "U7") (pin "3") (pinfunction "V_S+_3") (pintype "power_in"))
    )
    (net (code "7") (name "A3V3_RF") (class "Default")
      (node (ref "C101") (pin "+") (pinfunction "+_+") (pintype "passive"))
      (node (ref "C102") (pin "1") (pinfunction "1_1") (pintype "passive"))
      (node (ref "C103") (pin "1") (pinfunction "1_1") (pintype "passive"))
      (node (ref "C104") (pin "1") (pinfunction "1_1") (pintype "passive"))
      (node (ref "C105") (pin "2") (pinfunction "2_2") (pintype "passive"))
      (node (ref "C106") (pin "2") (pinfunction "2_2") (pintype "passive"))
      (node (ref "C107") (pin "1") (pinfunction "1_1") (pintype "passive"))
      (node (ref "C108") (pin "1") (pinfunction "1_1") (pintype "passive"))
      (node (ref "C109") (pin "1") (pinfunction "1_1") (pintype "passive"))
      (node (ref "C110") (pin "1") (pinfunction "1_1") (pintype "passive"))
      (node (ref "C111") (pin "1") (pinfunction "1_1") (pintype "passive"))
      (node (ref "C112") (pin "1") (pinfunction "1_1") (pintype "passive"))
      (node (ref "C113") (pin "1") (pinfunction "1_1") (pintype "passive"))
      (node (ref "C114") (pin "1") (pinfunction "1_1") (pintype "passive"))
      (node (ref "C115") (pin "1") (pinfunction "1_1") (pintype "passive"))
      (node (ref "C116") (pin "1") (pinfunction "1_1") (pintype "passive"))
      (node (ref "R9") (pin "2") (pinfunction "2_2") (pintype "passive"))
      (node (ref "U1") (pin "1") (pinfunction "VCCLNA_1") (pintype "power_in"))
      (node (ref "U1") (pin "13") (pinfunction "VCCTXPA_13") (pintype "power_in"))
      (node (ref "U1") (pin "17") (pinfunction "VCCTXMX_17") (pintype "power_in"))
      (node (ref "U1") (pin "20") (pinfunction "VCCPLL_20") (pintype "power_in"))
      (node (ref "U1") (pin "25") (pinfunction "VCCCP_25") (pintype "power_in"))
      (node (ref "U1") (pin "27") (pinfunction "VCCXTAL_27") (pintype "power_in"))
      (node (ref "U1") (pin "30") (pinfunction "VCCVCO_30") (pintype "power_in"))
      (node (ref "U1") (pin "39") (pinfunction "VCCRXVGA_39") (pintype "power_in"))
      (node (ref "U1") (pin "41") (pinfunction "VCCRXFL_41") (pintype "power_in"))
      (node (ref "U1") (pin "46") (pinfunction "VCCRXMX_46") (pintype "power_in"))
      (node (ref "U1") (pin "7") (pinfunction "VCCPA_7") (pintype "power_in"))
    )
    (net (code "8") (name "ADC3+") (class "Default")
      (node (ref "J1") (pin "70") (pinfunction "70_70") (pintype "passive"))
      (node (ref "R47") (pin "2") (pinfunction "2_2") (pintype "passive"))
    )
    (net (code "9") (name "ADC3-") (class "Default")
      (node (ref "J1") (pin "68") (pinfunction "68_68") (pintype "passive"))
      (node (ref "R48") (pin "2") (pinfunction "2_2") (pintype "passive"))
    )
    (net (code "10") (name "ADC4+") (class "Default")
      (node (ref "J1") (pin "76") (pinfunction "76_76") (pintype "passive"))
      (node (ref "R57") (pin "2") (pinfunction "2_2") (pintype "passive"))
    )
    (net (code "11") (name "ADC4-") (class "Default")
      (node (ref "J1") (pin "74") (pinfunction "74_74") (pintype "passive"))
      (node (ref "R58") (pin "2") (pinfunction "2_2") (pintype "passive"))
    )
    (net (code "12") (name "AGND") (class "Default")
      (node (ref "C101") (pin "-") (pinfunction "-_-") (pintype "passive"))
      (node (ref "C102") (pin "2") (pinfunction "2_2") (pintype "passive"))
      (node (ref "C103") (pin "2") (pinfunction "2_2") (pintype "passive"))
      (node (ref "C104") (pin "2") (pinfunction "2_2") (pintype "passive"))
      (node (ref "C105") (pin "1") (pinfunction "1_1") (pintype "passive"))
      (node (ref "C106") (pin "1") (pinfunction "1_1") (pintype "passive"))
      (node (ref "C107") (pin "2") (pinfunction "2_2") (pintype "passive"))
      (node (ref "C108") (pin "2") (pinfunction "2_2") (pintype "passive"))
      (node (ref "C109") (pin "2") (pinfunction "2_2") (pintype "passive"))
      (node (ref "C110") (pin "2") (pinfunction "2_2") (pintype "passive"))
      (node (ref "C111") (pin "2") (pinfunction "2_2") (pintype "passive"))
      (node (ref "C112") (pin "2") (pinfunction "2_2") (pintype "passive"))
      (node (ref "C113") (pin "2") (pinfunction "2_2") (pintype "passive"))
      (node (ref "C114") (pin "2") (pinfunction "2_2") (pintype "passive"))
      (node (ref "C115") (pin "2") (pinfunction "2_2") (pintype "passive"))
      (node (ref "C116") (pin "2") (pinfunction "2_2") (pintype "passive"))
      (node (ref "C117") (pin "2") (pinfunction "2_2") (pintype "passive"))
      (node (ref "C118") (pin "2") (pinfunction "2_2") (pintype "passive"))
      (node (ref "C119") (pin "2") (pinfunction "2_2") (pintype "passive"))
      (node (ref "C120") (pin "2") (pinfunction "2_2") (pintype "passive"))
      (node (ref "C41") (pin "-") (pinfunction "-_-") (pintype "passive"))
      (node (ref "C42") (pin "2") (pinfunction "2_2") (pintype "passive"))
      (node (ref "C43") (pin "2") (pinfunction "2_2") (pintype "passive"))
      (node (ref "C45") (pin "2") (pinfunction "2_2") (pintype "passive"))
      (node (ref "C51") (pin "-") (pinfunction "-_-") (pintype "passive"))
      (node (ref "C52") (pin "2") (pinfunction "2_2") (pintype "passive"))
      (node (ref "C53") (pin "2") (pinfunction "2_2") (pintype "passive"))
      (node (ref "C61") (pin "-") (pinfunction "-_-") (pintype "passive"))
      (node (ref "C62") (pin "2") (pinfunction "2_2") (pintype "passive"))
      (node (ref "C63") (pin "2") (pinfunction "2_2") (pintype "passive"))
      (node (ref "C64") (pin "2") (pinfunction "2_2") (pintype "passive"))
      (node (ref "C67") (pin "2") (pinfunction "2_2") (pintype "passive"))
      (node (ref "C71") (pin "-") (pinfunction "-_-") (pintype "passive"))
      (node (ref "C72") (pin "2") (pinfunction "2_2") (pintype "passive"))
      (node (ref "C73") (pin "2") (pinfunction "2_2") (pintype "passive"))
      (node (ref "C74") (pin "2") (pinfunction "2_2") (pintype "passive"))
      (node (ref "J1") (pin "29") (pinfunction "29_29") (pintype "passive"))
      (node (ref "J1") (pin "30") (pinfunction "30_30") (pintype "passive"))
      (node (ref "J1") (pin "35") (pinfunction "35_35") (pintype "passive"))
      (node (ref "J1") (pin "36") (pinfunction "36_36") (pintype "passive"))
      (node (ref "J1") (pin "41") (pinfunction "41_41") (pintype "passive"))
      (node (ref "J1") (pin "42") (pinfunction "42_42") (pintype "passive"))
      (node (ref "J1") (pin "47") (pinfunction "47_47") (pintype "passive"))
      (node (ref "J1") (pin "48") (pinfunction "48_48") (pintype "passive"))
      (node (ref "J1") (pin "53") (pinfunction "53_53") (pintype "passive"))
      (node (ref "J1") (pin "54") (pinfunction "54_54") (pintype "passive"))
      (node (ref "J1") (pin "59") (pinfunction "59_59") (pintype "passive"))
      (node (ref "J1") (pin "60") (pinfunction "60_60") (pintype "passive"))
      (node (ref "J1") (pin "65") (pinfunction "65_65") (pintype "passive"))
      (node (ref "J1") (pin "66") (pinfunction "66_66") (pintype "passive"))
      (node (ref "J1") (pin "71") (pinfunction "71_71") (pintype "passive"))
      (node (ref "J1") (pin "72") (pinfunction "72_72") (pintype "passive"))
      (node (ref "J1") (pin "77") (pinfunction "77_77") (pintype "passive"))
      (node (ref "J1") (pin "78") (pinfunction "78_78") (pintype "passive"))
      (node (ref "J1") (pin "83") (pinfunction "83_83") (pintype "passive"))
      (node (ref "J1") (pin "84") (pinfunction "84_84") (pintype "passive"))
      (node (ref "R4") (pin "2") (pinfunction "2_2") (pintype "passive"))
      (node (ref "R41") (pin "1") (pinfunction "1_1") (pintype "passive"))
      (node (ref "R42") (pin "1") (pinfunction "1_1") (pintype "passive"))
      (node (ref "R452") (pin "1") (pinfunction "1_1") (pintype "passive"))
      (node (ref "R51") (pin "1") (pinfunction "1_1") (pintype "passive"))
      (node (ref "R52") (pin "1") (pinfunction "1_1") (pintype "passive"))
      (node (ref "R672") (pin "1") (pinfunction "1_1") (pintype "passive"))
      (node (ref "U1") (pin "2") (pinfunction "GNDRXLNA_2") (pintype "power_in"))
      (node (ref "U1") (pin "26") (pinfunction "GNDCP_26") (pintype "power_in"))
      (node (ref "U1") (pin "31") (pinfunction "GNDVCO_31") (pintype "power_in"))
      (node (ref "U1") (pin "49") (pinfunction "EP_49") (pintype "power_in"))
      (node (ref "U2") (pin "2") (pinfunction "2_2") (pintype "power_in"))
      (node (ref "U2") (pin "5") (pinfunction "5_5") (pintype "power_in"))
      (node (ref "U3") (pin "2") (pinfunction "2_2") (pintype "power_in"))
      (node (ref "U3") (pin "5") (pinfunction "5_5") (pintype "power_in"))
      (node (ref "U4") (pin "6") (pinfunction "V_S-_6") (pintype "power_in"))
      (node (ref "U5") (pin "6") (pinfunction "V_S-_6") (pintype "power_in"))
      (node (ref "U6") (pin "6") (pinfunction "V_S-_6") (pintype "power_in"))
      (node (ref "U7") (pin "6") (pinfunction "V_S-_6") (pintype "power_in"))
      (node (ref "X1") (pin "2@1") (pinfunction "GND_2@1") (pintype "power_in"))
      (node (ref "X1") (pin "2@2") (pinfunction "GND_2@2") (pintype "power_in"))
      (node (ref "X1") (pin "2@3") (pinfunction "GND_2@3") (pintype "power_in"))
      (node (ref "X1") (pin "2@4") (pinfunction "GND_2@4") (pintype "power_in"))
      (node (ref "X1") (pin "2@5") (pinfunction "GND_2@5") (pintype "power_in"))
      (node (ref "X1") (pin "2@6") (pinfunction "GND_2@6") (pintype "power_in"))
      (node (ref "X2") (pin "2@1") (pinfunction "GND_2@1") (pintype "power_in"))
      (node (ref "X2") (pin "2@2") (pinfunction "GND_2@2") (pintype "power_in"))
      (node (ref "X2") (pin "2@3") (pinfunction "GND_2@3") (pintype "power_in"))
      (node (ref "X2") (pin "2@4") (pinfunction "GND_2@4") (pintype "power_in"))
      (node (ref "X2") (pin "2@5") (pinfunction "GND_2@5") (pintype "power_in"))
      (node (ref "X2") (pin "2@6") (pinfunction "GND_2@6") (pintype "power_in"))
      (node (ref "X4") (pin "2@1") (pinfunction "GND_2@1") (pintype "power_in"))
      (node (ref "X4") (pin "2@2") (pinfunction "GND_2@2") (pintype "power_in"))
      (node (ref "X4") (pin "2@3") (pinfunction "GND_2@3") (pintype "power_in"))
      (node (ref "X4") (pin "2@4") (pinfunction "GND_2@4") (pintype "power_in"))
      (node (ref "X4") (pin "2@5") (pinfunction "GND_2@5") (pintype "power_in"))
      (node (ref "X4") (pin "2@6") (pinfunction "GND_2@6") (pintype "power_in"))
      (node (ref "X5") (pin "2@1") (pinfunction "GND_2@1") (pintype "power_in"))
      (node (ref "X5") (pin "2@2") (pinfunction "GND_2@2") (pintype "power_in"))
      (node (ref "X5") (pin "2@3") (pinfunction "GND_2@3") (pintype "power_in"))
      (node (ref "X5") (pin "2@4") (pinfunction "GND_2@4") (pintype "power_in"))
      (node (ref "X5") (pin "2@5") (pinfunction "GND_2@5") (pintype "power_in"))
      (node (ref "X5") (pin "2@6") (pinfunction "GND_2@6") (pintype "power_in"))
      (node (ref "X6") (pin "2@1") (pinfunction "GND_2@1") (pintype "power_in"))
      (node (ref "X6") (pin "2@2") (pinfunction "GND_2@2") (pintype "power_in"))
      (node (ref "X6") (pin "2@3") (pinfunction "GND_2@3") (pintype "power_in"))
      (node (ref "X6") (pin "2@4") (pinfunction "GND_2@4") (pintype "power_in"))
      (node (ref "X6") (pin "2@5") (pinfunction "GND_2@5") (pintype "power_in"))
      (node (ref "X6") (pin "2@6") (pinfunction "GND_2@6") (pintype "power_in"))
      (node (ref "X7") (pin "2@1") (pinfunction "GND_2@1") (pintype "power_in"))
      (node (ref "X7") (pin "2@2") (pinfunction "GND_2@2") (pintype "power_in"))
      (node (ref "X7") (pin "2@3") (pinfunction "GND_2@3") (pintype "power_in"))
      (node (ref "X7") (pin "2@4") (pinfunction "GND_2@4") (pintype "power_in"))
      (node (ref "X7") (pin "2@5") (pinfunction "GND_2@5") (pintype "power_in"))
      (node (ref "X7") (pin "2@6") (pinfunction "GND_2@6") (pintype "power_in"))
    )
    (net (code "13") (name "ANTSEL") (class "Default")
      (node (ref "SW2") (pin "2") (pinfunction "2_2") (pintype "passive"))
      (node (ref "U1") (pin "47") (pinfunction "ANTSEL_47") (pintype "input"))
    )
    (net (code "14") (name "B1") (class "Default")
      (node (ref "J1") (pin "11") (pinfunction "11_11") (pintype "passive"))
      (node (ref "U1") (pin "23") (pinfunction "B1_23") (pintype "input"))
    )
    (net (code "15") (name "B2") (class "Default")
      (node (ref "J1") (pin "19") (pinfunction "19_19") (pintype "passive"))
      (node (ref "U1") (pin "11") (pinfunction "B2_11") (pintype "input"))
    )
    (net (code "16") (name "B3") (class "Default")
      (node (ref "J1") (pin "21") (pinfunction "21_21") (pintype "passive"))
      (node (ref "U1") (pin "8") (pinfunction "B3_8") (pintype "input"))
    )
    (net (code "17") (name "B4") (class "Default")
      (node (ref "J1") (pin "15") (pinfunction "15_15") (pintype "passive"))
      (node (ref "U1") (pin "34") (pinfunction "B4_34") (pintype "input"))
    )
    (net (code "18") (name "B5") (class "Default")
      (node (ref "J1") (pin "16") (pinfunction "16_16") (pintype "passive"))
      (node (ref "U1") (pin "14") (pinfunction "B5_14") (pintype "input"))
    )
    (net (code "19") (name "B6") (class "Default")
      (node (ref "SW3") (pin "2") (pinfunction "2_2") (pintype "passive"))
      (node (ref "U1") (pin "3") (pinfunction "B6_3") (pintype "input"))
    )
    (net (code "20") (name "B7") (class "Default")
      (node (ref "SW4") (pin "2") (pinfunction "2_2") (pintype "passive"))
      (node (ref "U1") (pin "6") (pinfunction "B7_6") (pintype "input"))
    )
    (net (code "21") (name "BYPASS") (class "Default")
      (node (ref "C117") (pin "1") (pinfunction "1_1") (pintype "passive"))
      (node (ref "U1") (pin "33") (pinfunction "BYPASS_33") (pintype "power_in"))
    )
    (net (code "22") (name "CLK1") (class "Default")
      (node (ref "J1") (pin "12") (pinfunction "12_12") (pintype "passive"))
      (node (ref "X8") (pin "1") (pinfunction "1_1") (pintype "passive"))
    )
    (net (code "23") (name "CLK2") (class "Default")
      (node (ref "J1") (pin "14") (pinfunction "14_14") (pintype "passive"))
      (node (ref "R5") (pin "1") (pinfunction "1_1") (pintype "passive"))
      (node (ref "R6") (pin "1") (pinfunction "1_1") (pintype "passive"))
    )
    (net (code "24") (name "D1V5") (class "Default")
      (node (ref "J1") (pin "7") (pinfunction "7_7") (pintype "passive"))
      (node (ref "J1") (pin "8") (pinfunction "8_8") (pintype "passive"))
    )
    (net (code "25") (name "D3V3") (class "Default")
      (node (ref "IC1") (pin "8") (pinfunction "VCC_8") (pintype "power_in"))
      (node (ref "J1") (pin "5") (pinfunction "5_5") (pintype "passive"))
      (node (ref "J1") (pin "6") (pinfunction "6_6") (pintype "passive"))
      (node (ref "R1") (pin "2") (pinfunction "2_2") (pintype "passive"))
      (node (ref "R2") (pin "2") (pinfunction "2_2") (pintype "passive"))
      (node (ref "R7") (pin "2") (pinfunction "2_2") (pintype "passive"))
      (node (ref "RA01") (pin "1") (pinfunction "1_1") (pintype "passive"))
      (node (ref "RA11") (pin "1") (pinfunction "1_1") (pintype "passive"))
      (node (ref "RA21") (pin "1") (pinfunction "1_1") (pintype "passive"))
      (node (ref "RWP1") (pin "1") (pinfunction "1_1") (pintype "passive"))
      (node (ref "SW1") (pin "1") (pinfunction "1_1") (pintype "passive"))
      (node (ref "SW2") (pin "1") (pinfunction "1_1") (pintype "passive"))
      (node (ref "SW3") (pin "1") (pinfunction "1_1") (pintype "passive"))
      (node (ref "SW4") (pin "1") (pinfunction "1_1") (pintype "passive"))
    )
    (net (code "26") (name "DAC3+") (class "Default")
      (node (ref "J1") (pin "58") (pinfunction "58_58") (pintype "passive"))
      (node (ref "R62") (pin "1") (pinfunction "1_1") (pintype "passive"))
    )
    (net (code "27") (name "DAC3-") (class "Default")
      (node (ref "J1") (pin "56") (pinfunction "56_56") (pintype "passive"))
      (node (ref "R61") (pin "1") (pinfunction "1_1") (pintype "passive"))
    )
    (net (code "28") (name "DAC4+") (class "Default")
      (node (ref "J1") (pin "64") (pinfunction "64_64") (pintype "passive"))
      (node (ref "R72") (pin "1") (pinfunction "1_1") (pintype "passive"))
    )
    (net (code "29") (name "DAC4-") (class "Default")
      (node (ref "J1") (pin "62") (pinfunction "62_62") (pintype "passive"))
      (node (ref "R71") (pin "1") (pinfunction "1_1") (pintype "passive"))
    )
    (net (code "30") (name "DGND") (class "Default")
      (node (ref "C123") (pin "2") (pinfunction "2_2") (pintype "passive"))
      (node (ref "C124") (pin "2") (pinfunction "2_2") (pintype "passive"))
      (node (ref "C125") (pin "2") (pinfunction "2_2") (pintype "passive"))
      (node (ref "C126") (pin "1") (pinfunction "1_1") (pintype "passive"))
      (node (ref "IC1") (pin "4") (pinfunction "GND_4") (pintype "power_in"))
      (node (ref "J1") (pin "1") (pinfunction "1_1") (pintype "passive"))
      (node (ref "J1") (pin "10") (pinfunction "10_10") (pintype "passive"))
      (node (ref "J1") (pin "2") (pinfunction "2_2") (pintype "passive"))
      (node (ref "J1") (pin "9") (pinfunction "9_9") (pintype "passive"))
      (node (ref "R4") (pin "1") (pinfunction "1_1") (pintype "passive"))
      (node (ref "RA00") (pin "1") (pinfunction "1_1") (pintype "passive"))
      (node (ref "RA10") (pin "1") (pinfunction "1_1") (pintype "passive"))
      (node (ref "RA20") (pin "1") (pinfunction "1_1") (pintype "passive"))
      (node (ref "RWP0") (pin "1") (pinfunction "1_1") (pintype "passive"))
      (node (ref "SW1") (pin "3") (pinfunction "3_3") (pintype "passive"))
      (node (ref "SW2") (pin "3") (pinfunction "3_3") (pintype "passive"))
      (node (ref "SW3") (pin "3") (pinfunction "3_3") (pintype "passive"))
      (node (ref "SW4") (pin "3") (pinfunction "3_3") (pintype "passive"))
      (node (ref "X3") (pin "2") (pinfunction "GND_2") (pintype "power_in"))
      (node (ref "X8") (pin "2@1") (pinfunction "GND_2@1") (pintype "power_in"))
      (node (ref "X8") (pin "2@2") (pinfunction "GND_2@2") (pintype "power_in"))
      (node (ref "X8") (pin "2@3") (pinfunction "GND_2@3") (pintype "power_in"))
      (node (ref "X8") (pin "2@4") (pinfunction "GND_2@4") (pintype "power_in"))
      (node (ref "X8") (pin "2@5") (pinfunction "GND_2@5") (pintype "power_in"))
      (node (ref "X8") (pin "2@6") (pinfunction "GND_2@6") (pintype "power_in"))
      (node (ref "X9") (pin "1") (pinfunction "1_1") (pintype "passive"))
      (node (ref "X9") (pin "2") (pinfunction "2_2") (pintype "power_in"))
      (node (ref "X9") (pin "4") (pinfunction "4_4") (pintype "power_in"))
    )
    (net (code "31") (name "DIN") (class "Default")
      (node (ref "J1") (pin "20") (pinfunction "20_20") (pintype "passive"))
      (node (ref "U1") (pin "19") (pinfunction "DIN_19") (pintype "input"))
    )
    (net (code "32") (name "I2C_SCL") (class "Default")
      (node (ref "IC1") (pin "6") (pinfunction "SCL_6") (pintype "input"))
      (node (ref "J1") (pin "26") (pinfunction "26_26") (pintype "passive"))
      (node (ref "R1") (pin "1") (pinfunction "1_1") (pintype "passive"))
    )
    (net (code "33") (name "I2C_SDA") (class "Default")
      (node (ref "IC1") (pin "5") (pinfunction "SDA_5") (pintype "bidirectional"))
      (node (ref "J1") (pin "28") (pinfunction "28_28") (pintype "passive"))
      (node (ref "R2") (pin "1") (pinfunction "1_1") (pintype "passive"))
    )
    (net (code "34") (name "LD") (class "Default")
      (node (ref "J1") (pin "13") (pinfunction "13_13") (pintype "passive"))
      (node (ref "U1") (pin "22") (pinfunction "LD_22") (pintype "output"))
    )
    (net (code "35") (name "Net-(C64-Pad1)") (class "Default")
      (node (ref "C64") (pin "1") (pinfunction "1_1") (pintype "passive"))
      (node (ref "R65") (pin "2") (pinfunction "2_2") (pintype "passive"))
      (node (ref "R66") (pin "1") (pinfunction "1_1") (pintype "passive"))
    )
    (net (code "36") (name "Net-(C74-Pad1)") (class "Default")
      (node (ref "C74") (pin "1") (pinfunction "1_1") (pintype "passive"))
      (node (ref "R75") (pin "2") (pinfunction "2_2") (pintype "passive"))
      (node (ref "R76") (pin "1") (pinfunction "1_1") (pintype "passive"))
    )
    (net (code "37") (name "Net-(C119-Pad1)") (class "Default")
      (node (ref "C119") (pin "1") (pinfunction "1_1") (pintype "passive"))
      (node (ref "R102") (pin "2") (pinfunction "2_2") (pintype "passive"))
    )
    (net (code "38") (name "Net-(C128-Pad1)") (class "Default")
      (node (ref "C128") (pin "1") (pinfunction "1_1") (pintype "passive"))
      (node (ref "X9") (pin "3") (pinfunction "3_3") (pintype "passive"))
    )
    (net (code "39") (name "Net-(R41-Pad2)") (class "Default")
      (node (ref "R41") (pin "2") (pinfunction "2_2") (pintype "passive"))
      (node (ref "R43") (pin "1") (pinfunction "1_1") (pintype "passive"))
      (node (ref "X4") (pin "1") (pinfunction "1_1") (pintype "passive"))
    )
    (net (code "40") (name "Net-(R42-Pad2)") (class "Default")
      (node (ref "R42") (pin "2") (pinfunction "2_2") (pintype "passive"))
      (node (ref "R44") (pin "1") (pinfunction "1_1") (pintype "passive"))
    )
    (net (code "41") (name "Net-(R51-Pad2)") (class "Default")
      (node (ref "R51") (pin "2") (pinfunction "2_2") (pintype "passive"))
      (node (ref "R53") (pin "1") (pinfunction "1_1") (pintype "passive"))
      (node (ref "X5") (pin "1") (pinfunction "1_1") (pintype "passive"))
    )
    (net (code "42") (name "Net-(R52-Pad2)") (class "Default")
      (node (ref "R52") (pin "2") (pinfunction "2_2") (pintype "passive"))
      (node (ref "R54") (pin "1") (pinfunction "1_1") (pintype "passive"))
    )
    (net (code "43") (name "Net-(R66-Pad2)") (class "Default")
      (node (ref "R66") (pin "2") (pinfunction "2_2") (pintype "passive"))
      (node (ref "X6") (pin "1") (pinfunction "1_1") (pintype "passive"))
    )
    (net (code "44") (name "Net-(R76-Pad2)") (class "Default")
      (node (ref "R76") (pin "2") (pinfunction "2_2") (pintype "passive"))
      (node (ref "X7") (pin "1") (pinfunction "1_1") (pintype "passive"))
    )
    (net (code "45") (name "Net-(U1A-ANT1+)") (class "Default")
      (node (ref "U1") (pin "4") (pinfunction "ANT1+_4") (pintype "bidirectional"))
      (node (ref "U2") (pin "4") (pinfunction "4_4") (pintype "bidirectional"))
    )
    (net (code "46") (name "Net-(U1A-ANT1-)") (class "Default")
      (node (ref "U1") (pin "5") (pinfunction "ANT1-_5") (pintype "bidirectional"))
      (node (ref "U2") (pin "3") (pinfunction "3_3") (pintype "bidirectional"))
    )
    (net (code "47") (name "Net-(U1A-ANT2+)") (class "Default")
      (node (ref "U1") (pin "9") (pinfunction "ANT2+_9") (pintype "bidirectional"))
      (node (ref "U3") (pin "4") (pinfunction "4_4") (pintype "bidirectional"))
    )
    (net (code "48") (name "Net-(U1A-ANT2-)") (class "Default")
      (node (ref "U1") (pin "10") (pinfunction "ANT2-_10") (pintype "bidirectional"))
      (node (ref "U3") (pin "3") (pinfunction "3_3") (pintype "bidirectional"))
    )
    (net (code "49") (name "Net-(U1D-CLOCKOUT)") (class "Default")
      (node (ref "R5") (pin "2") (pinfunction "2_2") (pintype "passive"))
      (node (ref "U1") (pin "21") (pinfunction "CLOCKOUT_21") (pintype "output"))
    )
    (net (code "50") (name "Net-(U1D-CPOUT)") (class "Default")
      (node (ref "C120") (pin "1") (pinfunction "1_1") (pintype "passive"))
      (node (ref "R101") (pin "1") (pinfunction "1_1") (pintype "passive"))
      (node (ref "R102") (pin "1") (pinfunction "1_1") (pintype "passive"))
      (node (ref "U1") (pin "24") (pinfunction "CPOUT_24") (pintype "output"))
    )
    (net (code "51") (name "Net-(U1D-CTUNE)") (class "Default")
      (node (ref "C126") (pin "2") (pinfunction "2_2") (pintype "passive"))
      (node (ref "C127") (pin "1") (pinfunction "1_1") (pintype "passive"))
      (node (ref "U1") (pin "29") (pinfunction "CTUNE_29") (pintype "input"))
    )
    (net (code "52") (name "Net-(U1D-TUNE)") (class "Default")
      (node (ref "C118") (pin "1") (pinfunction "1_1") (pintype "passive"))
      (node (ref "R101") (pin "2") (pinfunction "2_2") (pintype "passive"))
      (node (ref "U1") (pin "32") (pinfunction "TUNE_32") (pintype "input"))
    )
    (net (code "53") (name "Net-(U1D-XTAL)") (class "Default")
      (node (ref "C121") (pin "1") (pinfunction "1_1") (pintype "passive"))
      (node (ref "C127") (pin "2") (pinfunction "2_2") (pintype "passive"))
      (node (ref "C128") (pin "2") (pinfunction "2_2") (pintype "passive"))
      (node (ref "U1") (pin "28") (pinfunction "XTAL_28") (pintype "input"))
    )
    (net (code "54") (name "Net-(U2-Pad1)") (class "Default")
      (node (ref "U2") (pin "1") (pinfunction "1_1") (pintype "bidirectional"))
      (node (ref "X1") (pin "1") (pinfunction "1_1") (pintype "passive"))
    )
    (net (code "55") (name "Net-(U3-Pad1)") (class "Default")
      (node (ref "U3") (pin "1") (pinfunction "1_1") (pintype "bidirectional"))
      (node (ref "X2") (pin "1") (pinfunction "1_1") (pintype "passive"))
    )
    (net (code "56") (name "Net-(U4-+IN)") (class "Default")
      (node (ref "R43") (pin "2") (pinfunction "2_2") (pintype "passive"))
      (node (ref "R45") (pin "1") (pinfunction "1_1") (pintype "passive"))
      (node (ref "U4") (pin "8") (pinfunction "+IN_8") (pintype "input"))
    )
    (net (code "57") (name "Net-(U4-+OUT)") (class "Default")
      (node (ref "R46") (pin "2") (pinfunction "2_2") (pintype "passive"))
      (node (ref "R48") (pin "1") (pinfunction "1_1") (pintype "passive"))
      (node (ref "U4") (pin "4") (pinfunction "+OUT_4") (pintype "output"))
    )
    (net (code "58") (name "Net-(U4--IN)") (class "Default")
      (node (ref "R44") (pin "2") (pinfunction "2_2") (pintype "passive"))
      (node (ref "R46") (pin "1") (pinfunction "1_1") (pintype "passive"))
      (node (ref "U4") (pin "1") (pinfunction "-IN_1") (pintype "input"))
    )
    (net (code "59") (name "Net-(U4--OUT)") (class "Default")
      (node (ref "R45") (pin "2") (pinfunction "2_2") (pintype "passive"))
      (node (ref "R47") (pin "1") (pinfunction "1_1") (pintype "passive"))
      (node (ref "U4") (pin "5") (pinfunction "-OUT_5") (pintype "output"))
    )
    (net (code "60") (name "Net-(U5-+IN)") (class "Default")
      (node (ref "R53") (pin "2") (pinfunction "2_2") (pintype "passive"))
      (node (ref "R55") (pin "1") (pinfunction "1_1") (pintype "passive"))
      (node (ref "U5") (pin "8") (pinfunction "+IN_8") (pintype "input"))
    )
    (net (code "61") (name "Net-(U5-+OUT)") (class "Default")
      (node (ref "R56") (pin "2") (pinfunction "2_2") (pintype "passive"))
      (node (ref "R58") (pin "1") (pinfunction "1_1") (pintype "passive"))
      (node (ref "U5") (pin "4") (pinfunction "+OUT_4") (pintype "output"))
    )
    (net (code "62") (name "Net-(U5--IN)") (class "Default")
      (node (ref "R54") (pin "2") (pinfunction "2_2") (pintype "passive"))
      (node (ref "R56") (pin "1") (pinfunction "1_1") (pintype "passive"))
      (node (ref "U5") (pin "1") (pinfunction "-IN_1") (pintype "input"))
    )
    (net (code "63") (name "Net-(U5--OUT)") (class "Default")
      (node (ref "R55") (pin "2") (pinfunction "2_2") (pintype "passive"))
      (node (ref "R57") (pin "1") (pinfunction "1_1") (pintype "passive"))
      (node (ref "U5") (pin "5") (pinfunction "-OUT_5") (pintype "output"))
    )
    (net (code "64") (name "Net-(U6-+IN)") (class "Default")
      (node (ref "R61") (pin "2") (pinfunction "2_2") (pintype "passive"))
      (node (ref "R63") (pin "1") (pinfunction "1_1") (pintype "passive"))
      (node (ref "U6") (pin "8") (pinfunction "+IN_8") (pintype "input"))
    )
    (net (code "65") (name "Net-(U6-+OUT)") (class "Default")
      (node (ref "R64") (pin "2") (pinfunction "2_2") (pintype "passive"))
      (node (ref "U6") (pin "4") (pinfunction "+OUT_4") (pintype "output"))
    )
    (net (code "66") (name "Net-(U6--IN)") (class "Default")
      (node (ref "R62") (pin "2") (pinfunction "2_2") (pintype "passive"))
      (node (ref "R64") (pin "1") (pinfunction "1_1") (pintype "passive"))
      (node (ref "U6") (pin "1") (pinfunction "-IN_1") (pintype "input"))
    )
    (net (code "67") (name "Net-(U6--OUT)") (class "Default")
      (node (ref "R63") (pin "2") (pinfunction "2_2") (pintype "passive"))
      (node (ref "R65") (pin "1") (pinfunction "1_1") (pintype "passive"))
      (node (ref "U6") (pin "5") (pinfunction "-OUT_5") (pintype "output"))
    )
    (net (code "68") (name "Net-(U7-+IN)") (class "Default")
      (node (ref "R71") (pin "2") (pinfunction "2_2") (pintype "passive"))
      (node (ref "R73") (pin "1") (pinfunction "1_1") (pintype "passive"))
      (node (ref "U7") (pin "8") (pinfunction "+IN_8") (pintype "input"))
    )
    (net (code "69") (name "Net-(U7-+OUT)") (class "Default")
      (node (ref "R74") (pin "2") (pinfunction "2_2") (pintype "passive"))
      (node (ref "U7") (pin "4") (pinfunction "+OUT_4") (pintype "output"))
    )
    (net (code "70") (name "Net-(U7--IN)") (class "Default")
      (node (ref "R72") (pin "2") (pinfunction "2_2") (pintype "passive"))
      (node (ref "R74") (pin "1") (pinfunction "1_1") (pintype "passive"))
      (node (ref "U7") (pin "1") (pinfunction "-IN_1") (pintype "input"))
    )
    (net (code "71") (name "Net-(U7--OUT)") (class "Default")
      (node (ref "R73") (pin "2") (pinfunction "2_2") (pintype "passive"))
      (node (ref "R75") (pin "1") (pinfunction "1_1") (pintype "passive"))
      (node (ref "U7") (pin "5") (pinfunction "-OUT_5") (pintype "output"))
    )
    (net (code "72") (name "Net-(X3-FO)") (class "Default")
      (node (ref "C121") (pin "2") (pinfunction "2_2") (pintype "passive"))
      (node (ref "R6") (pin "2") (pinfunction "2_2") (pintype "passive"))
      (node (ref "X3") (pin "3") (pinfunction "FO_3") (pintype "output"))
    )
    (net (code "73") (name "Net-(X3-VCC)") (class "Default")
      (node (ref "C123") (pin "1") (pinfunction "1_1") (pintype "passive"))
      (node (ref "C124") (pin "1") (pinfunction "1_1") (pintype "passive"))
      (node (ref "C125") (pin "1") (pinfunction "1_1") (pintype "passive"))
      (node (ref "R7") (pin "1") (pinfunction "1_1") (pintype "passive"))
      (node (ref "X3") (pin "4") (pinfunction "VCC_4") (pintype "power_in"))
    )
    (net (code "74") (name "RSSI") (class "Default")
      (node (ref "J1") (pin "39") (pinfunction "39_39") (pintype "passive"))
      (node (ref "U1") (pin "16") (pinfunction "RSSI_16") (pintype "output"))
    )
    (net (code "75") (name "RXBBI+") (class "Default")
      (node (ref "J1") (pin "52") (pinfunction "52_52") (pintype "passive"))
      (node (ref "U1") (pin "38") (pinfunction "RXBBI+_38") (pintype "output"))
    )
    (net (code "76") (name "RXBBI-") (class "Default")
      (node (ref "J1") (pin "50") (pinfunction "50_50") (pintype "passive"))
      (node (ref "U1") (pin "37") (pinfunction "RXBBI-_37") (pintype "output"))
    )
    (net (code "77") (name "RXBBQ+") (class "Default")
      (node (ref "J1") (pin "46") (pinfunction "46_46") (pintype "passive"))
      (node (ref "U1") (pin "36") (pinfunction "RXBBQ+_36") (pintype "output"))
    )
    (net (code "78") (name "RXBBQ-") (class "Default")
      (node (ref "J1") (pin "44") (pinfunction "44_44") (pintype "passive"))
      (node (ref "U1") (pin "35") (pinfunction "RXBBQ-_35") (pintype "output"))
    )
    (net (code "79") (name "RXHP") (class "Default")
      (node (ref "SW1") (pin "2") (pinfunction "2_2") (pintype "passive"))
      (node (ref "U1") (pin "40") (pinfunction "RXHP_40") (pintype "input"))
    )
    (net (code "80") (name "RXTX") (class "Default")
      (node (ref "J1") (pin "23") (pinfunction "23_23") (pintype "passive"))
      (node (ref "U1") (pin "48") (pinfunction "RXTX_48") (pintype "input"))
    )
    (net (code "81") (name "SCLK") (class "Default")
      (node (ref "J1") (pin "18") (pinfunction "18_18") (pintype "passive"))
      (node (ref "U1") (pin "18") (pinfunction "SCLK_18") (pintype "input"))
    )
    (net (code "82") (name "TXBBI+") (class "Default")
      (node (ref "J1") (pin "40") (pinfunction "40_40") (pintype "passive"))
      (node (ref "U1") (pin "45") (pinfunction "TXBBI+_45") (pintype "input"))
    )
    (net (code "83") (name "TXBBI-") (class "Default")
      (node (ref "J1") (pin "38") (pinfunction "38_38") (pintype "passive"))
      (node (ref "U1") (pin "44") (pinfunction "TXBBI-_44") (pintype "input"))
    )
    (net (code "84") (name "TXBBQ+") (class "Default")
      (node (ref "J1") (pin "34") (pinfunction "34_34") (pintype "passive"))
      (node (ref "U1") (pin "43") (pinfunction "TXBBQ+_43") (pintype "input"))
    )
    (net (code "85") (name "TXBBQ-") (class "Default")
      (node (ref "J1") (pin "32") (pinfunction "32_32") (pintype "passive"))
      (node (ref "U1") (pin "42") (pinfunction "TXBBQ-_42") (pintype "input"))
    )
    (net (code "86") (name "VSUP") (class "Default")
      (node (ref "J1") (pin "3") (pinfunction "3_3") (pintype "passive"))
      (node (ref "J1") (pin "4") (pinfunction "4_4") (pintype "passive"))
    )
    (net (code "87") (name "V_BIAS_ADC") (class "Default")
      (node (ref "C45") (pin "1") (pinfunction "1_1") (pintype "passive"))
      (node (ref "R451") (pin "1") (pinfunction "1_1") (pintype "passive"))
      (node (ref "R452") (pin "2") (pinfunction "2_2") (pintype "passive"))
      (node (ref "U4") (pin "2") (pinfunction "V_OCM_2") (pintype "input"))
      (node (ref "U5") (pin "2") (pinfunction "V_OCM_2") (pintype "input"))
    )
    (net (code "88") (name "V_BIAS_DAC") (class "Default")
      (node (ref "C67") (pin "1") (pinfunction "1_1") (pintype "passive"))
      (node (ref "R671") (pin "1") (pinfunction "1_1") (pintype "passive"))
      (node (ref "R672") (pin "2") (pinfunction "2_2") (pintype "passive"))
      (node (ref "U6") (pin "2") (pinfunction "V_OCM_2") (pintype "input"))
      (node (ref "U7") (pin "2") (pinfunction "V_OCM_2") (pintype "input"))
    )
    (net (code "89") (name "WP") (class "Default")
      (node (ref "IC1") (pin "7") (pinfunction "WP_7") (pintype "input"))
      (node (ref "RWP0") (pin "2") (pinfunction "2_2") (pintype "passive"))
      (node (ref "RWP1") (pin "2") (pinfunction "2_2") (pintype "passive"))
    )
    (net (code "90") (name "unconnected-(J1-Pad22)") (class "Default")
      (node (ref "J1") (pin "22") (pinfunction "22_22") (pintype "passive"))
    )
    (net (code "91") (name "unconnected-(J1-Pad25)") (class "Default")
      (node (ref "J1") (pin "25") (pinfunction "25_25") (pintype "passive"))
    )
    (net (code "92") (name "unconnected-(J1-Pad27)") (class "Default")
      (node (ref "J1") (pin "27") (pinfunction "27_27") (pintype "passive"))
    )
    (net (code "93") (name "unconnected-(J1-Pad31)") (class "Default")
      (node (ref "J1") (pin "31") (pinfunction "31_31") (pintype "passive"))
    )
    (net (code "94") (name "unconnected-(J1-Pad33)") (class "Default")
      (node (ref "J1") (pin "33") (pinfunction "33_33") (pintype "passive"))
    )
    (net (code "95") (name "unconnected-(J1-Pad37)") (class "Default")
      (node (ref "J1") (pin "37") (pinfunction "37_37") (pintype "passive"))
    )
    (net (code "96") (name "unconnected-(J1-Pad43)") (class "Default")
      (node (ref "J1") (pin "43") (pinfunction "43_43") (pintype "passive"))
    )
    (net (code "97") (name "unconnected-(J1-Pad45)") (class "Default")
      (node (ref "J1") (pin "45") (pinfunction "45_45") (pintype "passive"))
    )
    (net (code "98") (name "unconnected-(J1-Pad49)") (class "Default")
      (node (ref "J1") (pin "49") (pinfunction "49_49") (pintype "passive"))
    )
    (net (code "99") (name "unconnected-(J1-Pad51)") (class "Default")
      (node (ref "J1") (pin "51") (pinfunction "51_51") (pintype "passive"))
    )
    (net (code "100") (name "unconnected-(J1-Pad55)") (class "Default")
      (node (ref "J1") (pin "55") (pinfunction "55_55") (pintype "passive"))
    )
    (net (code "101") (name "unconnected-(J1-Pad57)") (class "Default")
      (node (ref "J1") (pin "57") (pinfunction "57_57") (pintype "passive"))
    )
    (net (code "102") (name "unconnected-(J1-Pad61)") (class "Default")
      (node (ref "J1") (pin "61") (pinfunction "61_61") (pintype "passive"))
    )
    (net (code "103") (name "unconnected-(J1-Pad63)") (class "Default")
      (node (ref "J1") (pin "63") (pinfunction "63_63") (pintype "passive"))
    )
    (net (code "104") (name "unconnected-(J1-Pad67)") (class "Default")
      (node (ref "J1") (pin "67") (pinfunction "67_67") (pintype "passive"))
    )
    (net (code "105") (name "unconnected-(J1-Pad69)") (class "Default")
      (node (ref "J1") (pin "69") (pinfunction "69_69") (pintype "passive"))
    )
    (net (code "106") (name "unconnected-(J1-Pad73)") (class "Default")
      (node (ref "J1") (pin "73") (pinfunction "73_73") (pintype "passive"))
    )
    (net (code "107") (name "unconnected-(J1-Pad75)") (class "Default")
      (node (ref "J1") (pin "75") (pinfunction "75_75") (pintype "passive"))
    )
    (net (code "108") (name "unconnected-(U2-Pad6)") (class "Default")
      (node (ref "U2") (pin "6") (pinfunction "6_6") (pintype "no_connect"))
    )
    (net (code "109") (name "unconnected-(U3-Pad6)") (class "Default")
      (node (ref "U3") (pin "6") (pinfunction "6_6") (pintype "no_connect"))
    )
    (net (code "110") (name "unconnected-(U4-PD-Pad7)") (class "Default")
      (node (ref "U4") (pin "7") (pinfunction "PD_7") (pintype "input"))
    )
    (net (code "111") (name "unconnected-(U5-PD-Pad7)") (class "Default")
      (node (ref "U5") (pin "7") (pinfunction "PD_7") (pintype "input"))
    )
    (net (code "112") (name "unconnected-(U6-PD-Pad7)") (class "Default")
      (node (ref "U6") (pin "7") (pinfunction "PD_7") (pintype "input"))
    )
    (net (code "113") (name "unconnected-(U7-PD-Pad7)") (class "Default")
      (node (ref "U7") (pin "7") (pinfunction "PD_7") (pintype "input"))
    )
    (net (code "114") (name "unconnected-(X3-NC-Pad1)") (class "Default")
      (node (ref "X3") (pin "1") (pinfunction "NC_1") (pintype "no_connect"))
    )
    (net (code "115") (name "~{CS}") (class "Default")
      (node (ref "J1") (pin "24") (pinfunction "24_24") (pintype "passive"))
      (node (ref "U1") (pin "15") (pinfunction "/CS_15") (pintype "input"))
    )
    (net (code "116") (name "~{SHDN}") (class "Default")
      (node (ref "J1") (pin "17") (pinfunction "17_17") (pintype "passive"))
      (node (ref "U1") (pin "12") (pinfunction "/SHDN_12") (pintype "input"))
    )
  )
)
